# Baboi_v1_1.net
KiCad netlist of a schematic drawn in EAGLE
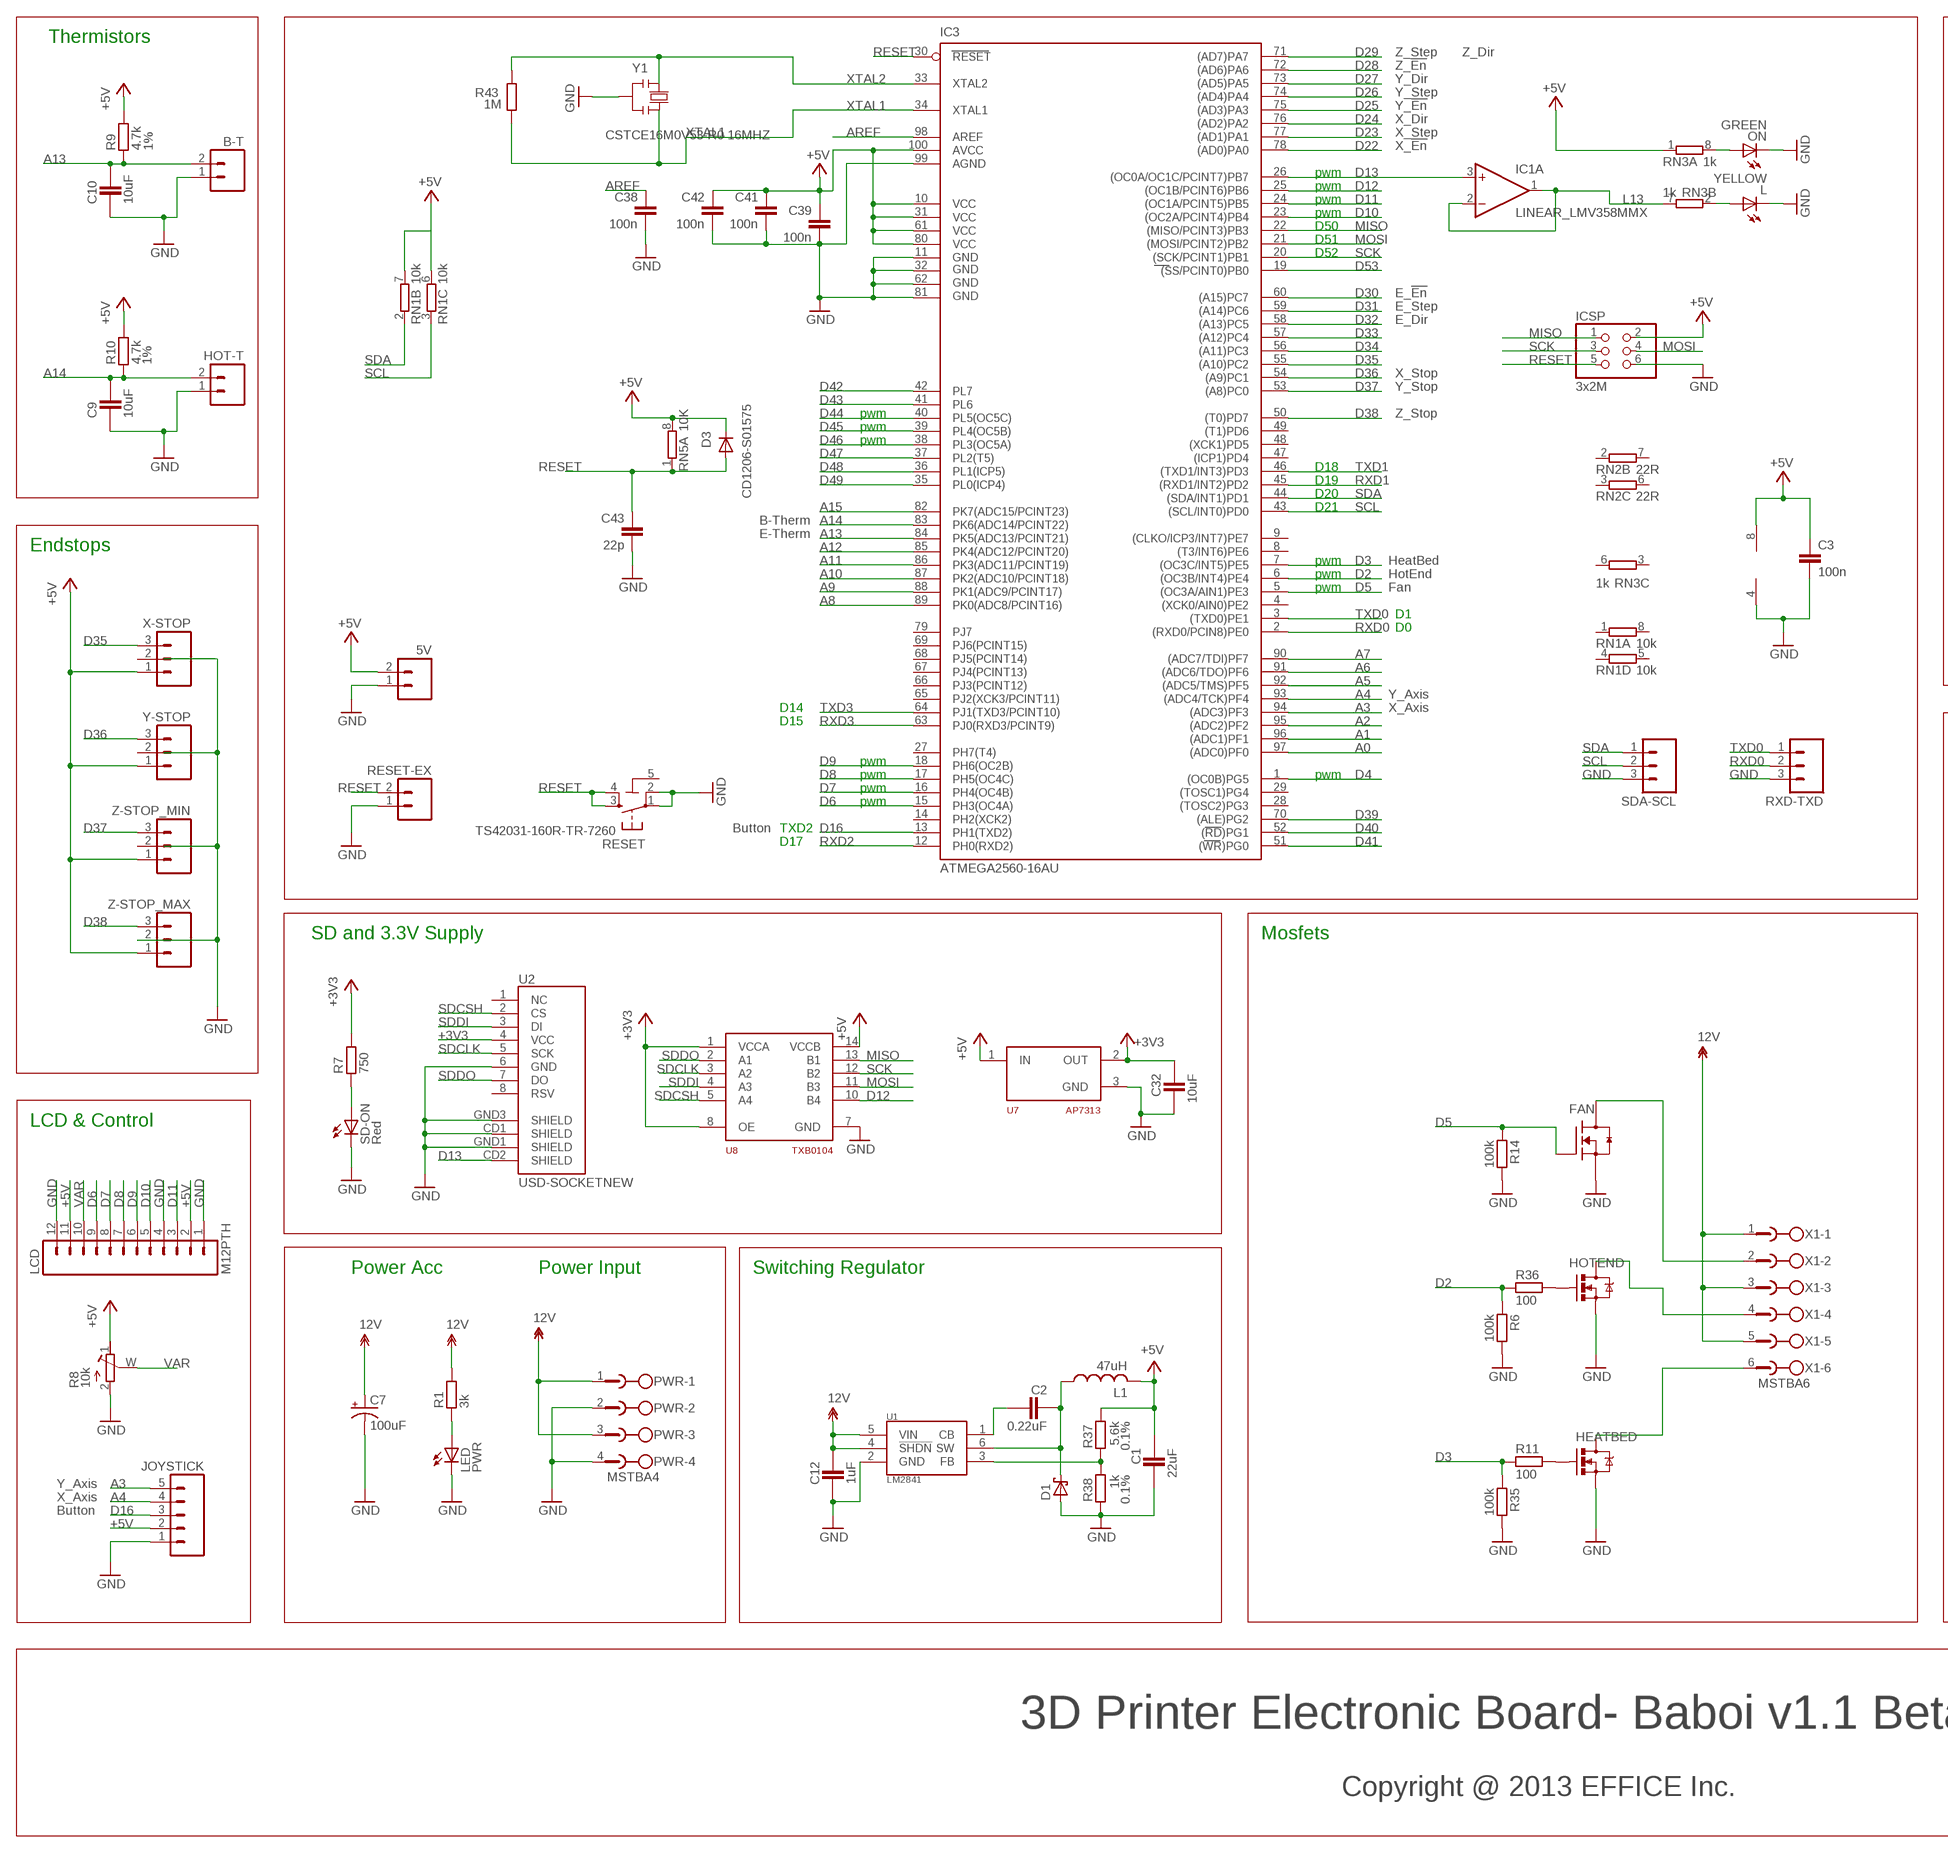
[diagram p0: schematic, sheet 1, part 1 of 2]
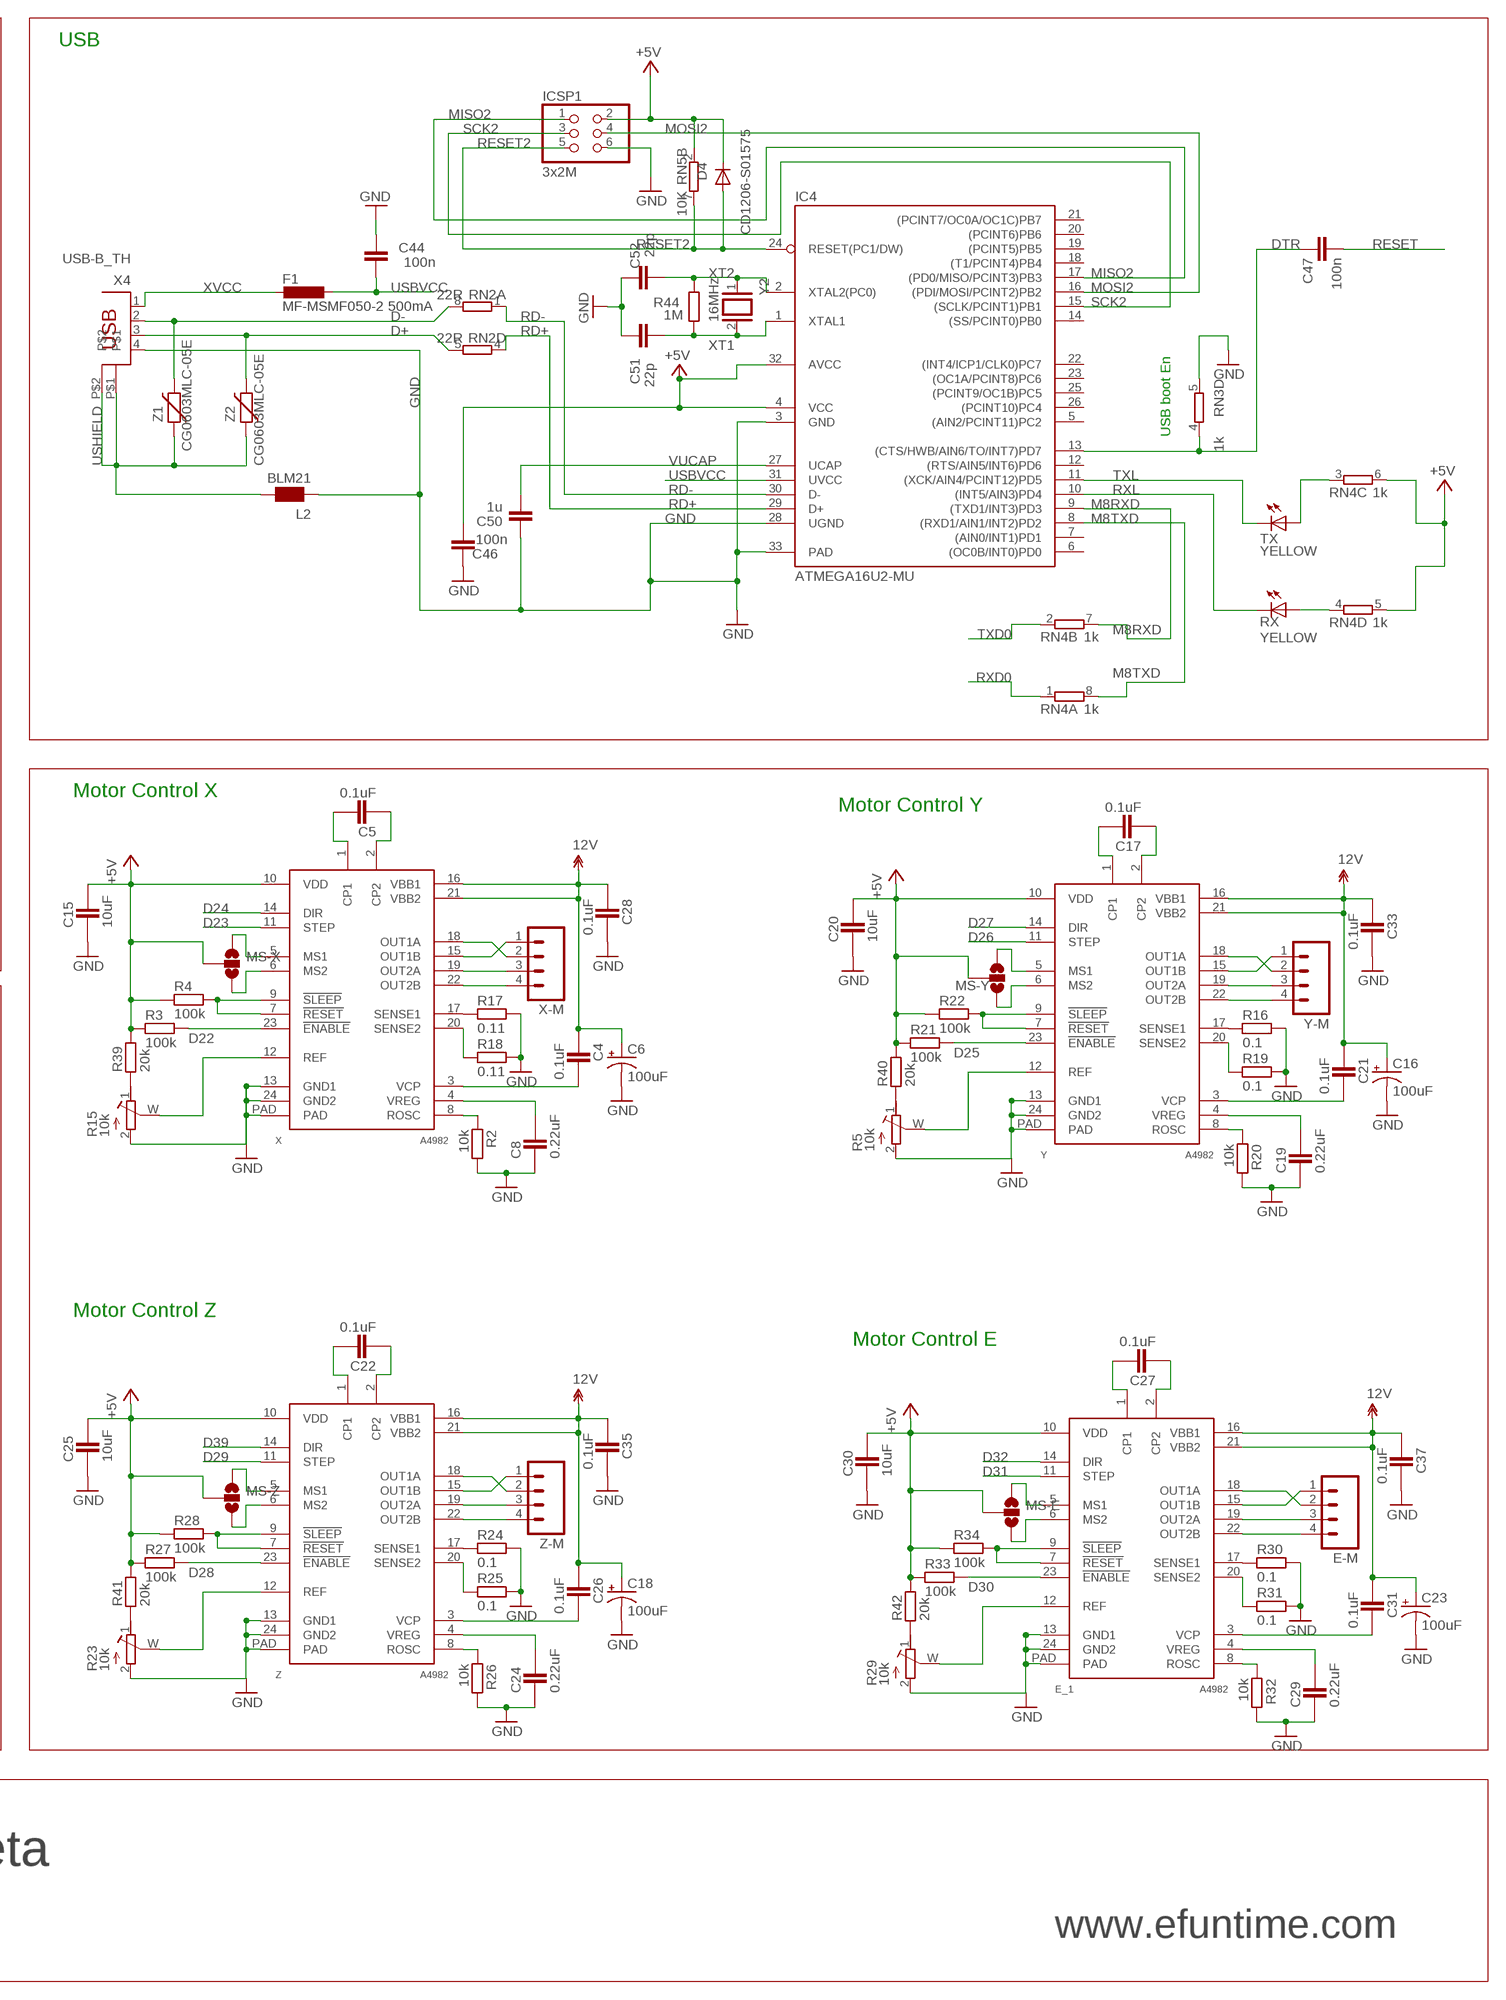
[diagram p1: schematic, sheet 1, part 2 of 2]

(export (version "E")
  (design (tool "Eeschema 10.0.6"))
  (components
    (comp (ref "5V")
      (value "M02PTH")
      (footprint "eagle-import:1X02")
      (libsource (lib "eagle-import") (part "M02PTH"))
    )
    (comp (ref "B-T")
      (value "M02PTH")
      (footprint "eagle-import:1X02")
      (libsource (lib "eagle-import") (part "M02PTH"))
    )
    (comp (ref "C1")
      (value "22uF")
      (footprint "eagle-import:CAPC2012X145AN")
      (libsource (lib "eagle-import") (part "CAPACITOR_0805"))
    )
    (comp (ref "C2")
      (value "0.22uF")
      (footprint "eagle-import:CAPC2012X145AN")
      (libsource (lib "eagle-import") (part "CAPACITOR_0805"))
    )
    (comp (ref "C3")
      (value "100n")
      (footprint "eagle-import:SMARTPRJ_C0603-ROUND")
      (libsource (lib "eagle-import") (part "SMARTPRJ_C-EUC0603"))
    )
    (comp (ref "C4")
      (value "0.1uF")
      (footprint "eagle-import:CAPC2012X145AN")
      (libsource (lib "eagle-import") (part "CAPACITOR_0805"))
    )
    (comp (ref "C5")
      (value "0.1uF")
      (footprint "eagle-import:CAPC2012X145AN")
      (libsource (lib "eagle-import") (part "CAPACITOR_0805"))
    )
    (comp (ref "C6")
      (value "100uF")
      (footprint "eagle-import:PANASONIC_D")
      (libsource (lib "eagle-import") (part "CPOL-USD"))
    )
    (comp (ref "C7")
      (value "100uF")
      (footprint "eagle-import:PANASONIC_D")
      (libsource (lib "eagle-import") (part "CPOL-USD"))
    )
    (comp (ref "C8")
      (value "0.22uF")
      (footprint "eagle-import:CAPC2012X145AN")
      (libsource (lib "eagle-import") (part "CAPACITOR_0805"))
    )
    (comp (ref "C9")
      (value "10uF")
      (footprint "eagle-import:CAPC2012X145AN")
      (libsource (lib "eagle-import") (part "CAPACITOR_0805"))
    )
    (comp (ref "C10")
      (value "10uF")
      (footprint "eagle-import:CAPC2012X145AN")
      (libsource (lib "eagle-import") (part "CAPACITOR_0805"))
    )
    (comp (ref "C12")
      (value "1uF")
      (footprint "eagle-import:CAPC2012X145AN")
      (libsource (lib "eagle-import") (part "CAPACITOR_0805"))
    )
    (comp (ref "C15")
      (value "10uF")
      (footprint "eagle-import:CAPC2012X145AN")
      (libsource (lib "eagle-import") (part "CAPACITOR_0805"))
    )
    (comp (ref "C16")
      (value "100uF")
      (footprint "eagle-import:PANASONIC_D")
      (libsource (lib "eagle-import") (part "CPOL-USD"))
    )
    (comp (ref "C17")
      (value "0.1uF")
      (footprint "eagle-import:CAPC2012X145AN")
      (libsource (lib "eagle-import") (part "CAPACITOR_0805"))
    )
    (comp (ref "C18")
      (value "100uF")
      (footprint "eagle-import:PANASONIC_D")
      (libsource (lib "eagle-import") (part "CPOL-USD"))
    )
    (comp (ref "C19")
      (value "0.22uF")
      (footprint "eagle-import:CAPC2012X145AN")
      (libsource (lib "eagle-import") (part "CAPACITOR_0805"))
    )
    (comp (ref "C20")
      (value "10uF")
      (footprint "eagle-import:CAPC2012X145AN")
      (libsource (lib "eagle-import") (part "CAPACITOR_0805"))
    )
    (comp (ref "C21")
      (value "0.1uF")
      (footprint "eagle-import:CAPC2012X145AN")
      (libsource (lib "eagle-import") (part "CAPACITOR_0805"))
    )
    (comp (ref "C22")
      (value "0.1uF")
      (footprint "eagle-import:CAPC2012X145AN")
      (libsource (lib "eagle-import") (part "CAPACITOR_0805"))
    )
    (comp (ref "C23")
      (value "100uF")
      (footprint "eagle-import:PANASONIC_D")
      (libsource (lib "eagle-import") (part "CPOL-USD"))
    )
    (comp (ref "C24")
      (value "0.22uF")
      (footprint "eagle-import:CAPC2012X145AN")
      (libsource (lib "eagle-import") (part "CAPACITOR_0805"))
    )
    (comp (ref "C25")
      (value "10uF")
      (footprint "eagle-import:CAPC2012X145AN")
      (libsource (lib "eagle-import") (part "CAPACITOR_0805"))
    )
    (comp (ref "C26")
      (value "0.1uF")
      (footprint "eagle-import:CAPC2012X145AN")
      (libsource (lib "eagle-import") (part "CAPACITOR_0805"))
    )
    (comp (ref "C27")
      (value "0.1uF")
      (footprint "eagle-import:CAPC2012X145AN")
      (libsource (lib "eagle-import") (part "CAPACITOR_0805"))
    )
    (comp (ref "C28")
      (value "0.1uF")
      (footprint "eagle-import:CAPC2012X145AN")
      (libsource (lib "eagle-import") (part "CAPACITOR_0805"))
    )
    (comp (ref "C29")
      (value "0.22uF")
      (footprint "eagle-import:CAPC2012X145AN")
      (libsource (lib "eagle-import") (part "CAPACITOR_0805"))
    )
    (comp (ref "C30")
      (value "10uF")
      (footprint "eagle-import:CAPC2012X145AN")
      (libsource (lib "eagle-import") (part "CAPACITOR_0805"))
    )
    (comp (ref "C31")
      (value "0.1uF")
      (footprint "eagle-import:CAPC2012X145AN")
      (libsource (lib "eagle-import") (part "CAPACITOR_0805"))
    )
    (comp (ref "C32")
      (value "10uF")
      (footprint "eagle-import:CAPC2012X145AN")
      (libsource (lib "eagle-import") (part "CAPACITOR_0805"))
    )
    (comp (ref "C33")
      (value "0.1uF")
      (footprint "eagle-import:CAPC2012X145AN")
      (libsource (lib "eagle-import") (part "CAPACITOR_0805"))
    )
    (comp (ref "C35")
      (value "0.1uF")
      (footprint "eagle-import:CAPC2012X145AN")
      (libsource (lib "eagle-import") (part "CAPACITOR_0805"))
    )
    (comp (ref "C37")
      (value "0.1uF")
      (footprint "eagle-import:CAPC2012X145AN")
      (libsource (lib "eagle-import") (part "CAPACITOR_0805"))
    )
    (comp (ref "C38")
      (value "100n")
      (footprint "eagle-import:C0603-ROUND")
      (libsource (lib "eagle-import") (part "C-EU0603-RND"))
    )
    (comp (ref "C39")
      (value "100n")
      (footprint "eagle-import:C0603-ROUND")
      (libsource (lib "eagle-import") (part "C-EU0603-RND"))
    )
    (comp (ref "C41")
      (value "100n")
      (footprint "eagle-import:C0603-ROUND")
      (libsource (lib "eagle-import") (part "C-EU0603-RND"))
    )
    (comp (ref "C42")
      (value "100n")
      (footprint "eagle-import:C0603-ROUND")
      (libsource (lib "eagle-import") (part "C-EU0603-RND"))
    )
    (comp (ref "C43")
      (value "22p")
      (footprint "eagle-import:C0603-ROUND")
      (libsource (lib "eagle-import") (part "C-EU0603-RND"))
    )
    (comp (ref "C44")
      (value "100n")
      (footprint "eagle-import:C0603-ROUND")
      (libsource (lib "eagle-import") (part "C-EU0603-RND"))
    )
    (comp (ref "C46")
      (value "100n")
      (footprint "eagle-import:C0603-ROUND")
      (libsource (lib "eagle-import") (part "C-EU0603-RND"))
    )
    (comp (ref "C47")
      (value "100n")
      (footprint "eagle-import:C0603-ROUND")
      (libsource (lib "eagle-import") (part "C-EU0603-RND"))
    )
    (comp (ref "C50")
      (value "1u")
      (footprint "eagle-import:C0603-ROUND")
      (libsource (lib "eagle-import") (part "C-EU0603-RND"))
    )
    (comp (ref "C51")
      (value "22p")
      (footprint "eagle-import:C0603-ROUND")
      (libsource (lib "eagle-import") (part "C-EU0603-RND"))
    )
    (comp (ref "C52")
      (value "22p")
      (footprint "eagle-import:C0603-ROUND")
      (libsource (lib "eagle-import") (part "C-EU0603-RND"))
    )
    (comp (ref "D1")
      (value "SCH-DIODESMA")
      (footprint "eagle-import:SMA")
      (libsource (lib "eagle-import") (part "SCH-DIODESMA"))
    )
    (comp (ref "D3")
      (value "CD1206-S01575")
      (footprint "eagle-import:MINIMELF")
      (libsource (lib "eagle-import") (part "DIODE-MINIMELF"))
    )
    (comp (ref "D4")
      (value "CD1206-S01575")
      (footprint "eagle-import:MINIMELF")
      (libsource (lib "eagle-import") (part "DIODE-MINIMELF"))
    )
    (comp (ref "E-M")
      (value "M04PTH")
      (footprint "eagle-import:1X04")
      (libsource (lib "eagle-import") (part "M04PTH"))
    )
    (comp (ref "E_1")
      (value "A4982")
      (footprint "eagle-import:TSSOP-24")
      (libsource (lib "eagle-import") (part "A4982"))
    )
    (comp (ref "F1")
      (value "MF-MSMF050-2 500mA")
      (footprint "eagle-import:L1812")
      (libsource (lib "eagle-import") (part "L-EUL1812"))
    )
    (comp (ref "FAN")
      (value "RFP30N06LE")
      (footprint "eagle-import:SOT95P280X135-3N")
      (libsource (lib "eagle-import") (part "MOSFET-NCH_SOT-23"))
    )
    (comp (ref "HEATBED")
      (value "RFP30N06LE")
      (footprint "eagle-import:TO220V")
      (libsource (lib "eagle-import") (part "MOSFET-NCHANNELPTH2"))
    )
    (comp (ref "HOT-T")
      (value "M02PTH")
      (footprint "eagle-import:1X02")
      (libsource (lib "eagle-import") (part "M02PTH"))
    )
    (comp (ref "HOTEND")
      (value "RFP30N06LE")
      (footprint "eagle-import:TO220V")
      (libsource (lib "eagle-import") (part "MOSFET-NCHANNELPTH2"))
    )
    (comp (ref "IC1")
      (value "LINEAR_LMV358MMX")
      (footprint "eagle-import:LINEAR_MSOP08")
      (libsource (lib "eagle-import") (part "LINEAR_LMV358?MMX"))
    )
    (comp (ref "IC3")
      (value "ATMEGA2560-16AU")
      (footprint "eagle-import:TQFP100")
      (libsource (lib "eagle-import") (part "ATMEGA2560AU2560-16"))
    )
    (comp (ref "IC4")
      (value "ATMEGA16U2-MU")
      (footprint "eagle-import:MLF32")
      (libsource (lib "eagle-import") (part "ATMEGA16U2-MU"))
    )
    (comp (ref "ICSP")
      (value "3x2M")
      (footprint "eagle-import:2X03")
      (libsource (lib "eagle-import") (part "PINHD-2X3"))
    )
    (comp (ref "ICSP1")
      (value "3x2M")
      (footprint "eagle-import:2X03")
      (libsource (lib "eagle-import") (part "PINHD-2X3"))
    )
    (comp (ref "JOYSTICK")
      (value "M05PTH")
      (footprint "eagle-import:1X05")
      (libsource (lib "eagle-import") (part "M05PTH"))
    )
    (comp (ref "L")
      (value "YELLOW")
      (footprint "eagle-import:CHIP-LED0805")
      (libsource (lib "eagle-import") (part "LEDCHIP-LED0805"))
    )
    (comp (ref "L1")
      (value "47uH")
      (footprint "eagle-import:SDR1006")
      (libsource (lib "eagle-import") (part "L-US"))
    )
    (comp (ref "L2")
      (value "BLM21")
      (footprint "eagle-import:0805")
      (libsource (lib "eagle-import") (part "WE-CBF_0805"))
    )
    (comp (ref "LCD")
      (value "M12PTH")
      (footprint "eagle-import:1X12")
      (libsource (lib "eagle-import") (part "M12PTH"))
    )
    (comp (ref "LED")
      (value "PWR")
      (footprint "eagle-import:CHIP-LED0805")
      (libsource (lib "eagle-import") (part "LEDCHIP-LED0805"))
    )
    (comp (ref "MS-E")
      (value "SOLDERJUMPER_2WAYCONNECTED")
      (footprint "eagle-import:SJ_3_CONNECTED")
      (libsource (lib "eagle-import") (part "SOLDERJUMPER_2WAYCONNECTED"))
    )
    (comp (ref "MS-X")
      (value "SOLDERJUMPER_2WAYCONNECTED")
      (footprint "eagle-import:SJ_3_CONNECTED")
      (libsource (lib "eagle-import") (part "SOLDERJUMPER_2WAYCONNECTED"))
    )
    (comp (ref "MS-Y")
      (value "SOLDERJUMPER_2WAYCONNECTED")
      (footprint "eagle-import:SJ_3_CONNECTED")
      (libsource (lib "eagle-import") (part "SOLDERJUMPER_2WAYCONNECTED"))
    )
    (comp (ref "MS-Z")
      (value "SOLDERJUMPER_2WAYCONNECTED")
      (footprint "eagle-import:SJ_3_CONNECTED")
      (libsource (lib "eagle-import") (part "SOLDERJUMPER_2WAYCONNECTED"))
    )
    (comp (ref "ON")
      (value "GREEN")
      (footprint "eagle-import:CHIP-LED0805")
      (libsource (lib "eagle-import") (part "LEDCHIP-LED0805"))
    )
    (comp (ref "PWR")
      (value "MSTBA4")
      (footprint "eagle-import:MSTBA4")
      (fields (field (name "MF") "FARNELL") (field (name "MPN") "1757268"))
      (libsource (lib "eagle-import") (part "MSTBA4"))
    )
    (comp (ref "R1")
      (value "3k")
      (footprint "eagle-import:RESC2012X70N")
      (libsource (lib "eagle-import") (part "RESISTOR_0805"))
    )
    (comp (ref "R2")
      (value "10k")
      (footprint "eagle-import:RESC2012X70N")
      (libsource (lib "eagle-import") (part "RESISTOR_0805"))
    )
    (comp (ref "R3")
      (value "100k")
      (footprint "eagle-import:RESC2012X70N")
      (libsource (lib "eagle-import") (part "RESISTOR_0805"))
    )
    (comp (ref "R4")
      (value "100k")
      (footprint "eagle-import:RESC2012X70N")
      (libsource (lib "eagle-import") (part "RESISTOR_0805"))
    )
    (comp (ref "R5")
      (value "10k")
      (footprint "eagle-import:RTRIM-ST4ETB")
      (libsource (lib "eagle-import") (part "RTRIM-ST-4EA"))
    )
    (comp (ref "R6")
      (value "100k")
      (footprint "eagle-import:RESC2012X70N")
      (libsource (lib "eagle-import") (part "RESISTOR_0805"))
    )
    (comp (ref "R7")
      (value "750")
      (footprint "eagle-import:RESC2012X70N")
      (libsource (lib "eagle-import") (part "RESISTOR_0805"))
    )
    (comp (ref "R8")
      (value "10k")
      (footprint "eagle-import:RTRIM-ST4ETB")
      (libsource (lib "eagle-import") (part "RTRIM-ST-4EA"))
    )
    (comp (ref "R9")
      (value "4.7k")
      (footprint "eagle-import:RESC2012X70N")
      (fields (field (name "TOLERANCE") "1%"))
      (libsource (lib "eagle-import") (part "RESISTOR_0805"))
    )
    (comp (ref "R10")
      (value "4.7k")
      (footprint "eagle-import:RESC2012X70N")
      (fields (field (name "TOLERANCE") "1%"))
      (libsource (lib "eagle-import") (part "RESISTOR_0805"))
    )
    (comp (ref "R11")
      (value "100")
      (footprint "eagle-import:RESC2012X70N")
      (libsource (lib "eagle-import") (part "RESISTOR_0805"))
    )
    (comp (ref "R14")
      (value "100k")
      (footprint "eagle-import:RESC2012X70N")
      (libsource (lib "eagle-import") (part "RESISTOR_0805"))
    )
    (comp (ref "R15")
      (value "10k")
      (footprint "eagle-import:RTRIM-ST4ETB")
      (libsource (lib "eagle-import") (part "RTRIM-ST-4EA"))
    )
    (comp (ref "R16")
      (value "0.1")
      (footprint "eagle-import:RESC2012X70N")
      (libsource (lib "eagle-import") (part "RESISTOR_0805"))
    )
    (comp (ref "R17")
      (value "0.11")
      (footprint "eagle-import:RESC2012X70N")
      (libsource (lib "eagle-import") (part "RESISTOR_0805"))
    )
    (comp (ref "R18")
      (value "0.11")
      (footprint "eagle-import:RESC2012X70N")
      (libsource (lib "eagle-import") (part "RESISTOR_0805"))
    )
    (comp (ref "R19")
      (value "0.1")
      (footprint "eagle-import:RESC2012X70N")
      (libsource (lib "eagle-import") (part "RESISTOR_0805"))
    )
    (comp (ref "R20")
      (value "10k")
      (footprint "eagle-import:RESC2012X70N")
      (libsource (lib "eagle-import") (part "RESISTOR_0805"))
    )
    (comp (ref "R21")
      (value "100k")
      (footprint "eagle-import:RESC2012X70N")
      (libsource (lib "eagle-import") (part "RESISTOR_0805"))
    )
    (comp (ref "R22")
      (value "100k")
      (footprint "eagle-import:RESC2012X70N")
      (libsource (lib "eagle-import") (part "RESISTOR_0805"))
    )
    (comp (ref "R23")
      (value "10k")
      (footprint "eagle-import:RTRIM-ST4ETB")
      (libsource (lib "eagle-import") (part "RTRIM-ST-4EA"))
    )
    (comp (ref "R24")
      (value "0.1")
      (footprint "eagle-import:RESC2012X70N")
      (libsource (lib "eagle-import") (part "RESISTOR_0805"))
    )
    (comp (ref "R25")
      (value "0.1")
      (footprint "eagle-import:RESC2012X70N")
      (libsource (lib "eagle-import") (part "RESISTOR_0805"))
    )
    (comp (ref "R26")
      (value "10k")
      (footprint "eagle-import:RESC2012X70N")
      (libsource (lib "eagle-import") (part "RESISTOR_0805"))
    )
    (comp (ref "R27")
      (value "100k")
      (footprint "eagle-import:RESC2012X70N")
      (libsource (lib "eagle-import") (part "RESISTOR_0805"))
    )
    (comp (ref "R28")
      (value "100k")
      (footprint "eagle-import:RESC2012X70N")
      (libsource (lib "eagle-import") (part "RESISTOR_0805"))
    )
    (comp (ref "R29")
      (value "10k")
      (footprint "eagle-import:RTRIM-ST4ETB")
      (libsource (lib "eagle-import") (part "RTRIM-ST-4EA"))
    )
    (comp (ref "R30")
      (value "0.1")
      (footprint "eagle-import:RESC2012X70N")
      (libsource (lib "eagle-import") (part "RESISTOR_0805"))
    )
    (comp (ref "R31")
      (value "0.1")
      (footprint "eagle-import:RESC2012X70N")
      (libsource (lib "eagle-import") (part "RESISTOR_0805"))
    )
    (comp (ref "R32")
      (value "10k")
      (footprint "eagle-import:RESC2012X70N")
      (libsource (lib "eagle-import") (part "RESISTOR_0805"))
    )
    (comp (ref "R33")
      (value "100k")
      (footprint "eagle-import:RESC2012X70N")
      (libsource (lib "eagle-import") (part "RESISTOR_0805"))
    )
    (comp (ref "R34")
      (value "100k")
      (footprint "eagle-import:RESC2012X70N")
      (libsource (lib "eagle-import") (part "RESISTOR_0805"))
    )
    (comp (ref "R35")
      (value "100k")
      (footprint "eagle-import:RESC2012X70N")
      (libsource (lib "eagle-import") (part "RESISTOR_0805"))
    )
    (comp (ref "R36")
      (value "100")
      (footprint "eagle-import:RESC2012X70N")
      (libsource (lib "eagle-import") (part "RESISTOR_0805"))
    )
    (comp (ref "R37")
      (value "5.6k")
      (footprint "eagle-import:RESC2012X70N")
      (fields (field (name "TOLERANCE") "0.1%"))
      (libsource (lib "eagle-import") (part "RESISTOR_0805"))
    )
    (comp (ref "R38")
      (value "1k")
      (footprint "eagle-import:RESC2012X70N")
      (fields (field (name "TOLERANCE") "0.1%"))
      (libsource (lib "eagle-import") (part "RESISTOR_0805"))
    )
    (comp (ref "R39")
      (value "20k")
      (footprint "eagle-import:RESC2012X70N")
      (libsource (lib "eagle-import") (part "RESISTOR_0805"))
    )
    (comp (ref "R40")
      (value "20k")
      (footprint "eagle-import:RESC2012X70N")
      (libsource (lib "eagle-import") (part "RESISTOR_0805"))
    )
    (comp (ref "R41")
      (value "20k")
      (footprint "eagle-import:RESC2012X70N")
      (libsource (lib "eagle-import") (part "RESISTOR_0805"))
    )
    (comp (ref "R42")
      (value "20k")
      (footprint "eagle-import:RESC2012X70N")
      (libsource (lib "eagle-import") (part "RESISTOR_0805"))
    )
    (comp (ref "R43")
      (value "1M")
      (footprint "eagle-import:R0603-ROUND")
      (libsource (lib "eagle-import") (part "R-EU_R0603"))
    )
    (comp (ref "R44")
      (value "1M")
      (footprint "eagle-import:R0603-ROUND")
      (libsource (lib "eagle-import") (part "R-EU_R0603"))
    )
    (comp (ref "RESET")
      (value "TS42031-160R-TR-7260")
      (footprint "eagle-import:TS42")
      (libsource (lib "eagle-import") (part "TS42"))
    )
    (comp (ref "RESET-EX")
      (value "M02PTH")
      (footprint "eagle-import:1X02")
      (libsource (lib "eagle-import") (part "M02PTH"))
    )
    (comp (ref "RN1")
      (value "10k")
      (footprint "eagle-import:RESISTOR-DIL_CAT16")
      (libsource (lib "eagle-import") (part "RESISTOR-DIL_4R-NCAT16"))
    )
    (comp (ref "RN2")
      (value "22R")
      (footprint "eagle-import:CAY16")
      (libsource (lib "eagle-import") (part "4R-NCAY16"))
    )
    (comp (ref "RN3")
      (value "1k")
      (footprint "eagle-import:CAY16")
      (libsource (lib "eagle-import") (part "4R-NCAY16"))
    )
    (comp (ref "RN4")
      (value "1k")
      (footprint "eagle-import:CAY16")
      (libsource (lib "eagle-import") (part "4R-NCAY16"))
    )
    (comp (ref "RN5")
      (value "10K")
      (footprint "eagle-import:CAT16")
      (libsource (lib "eagle-import") (part "4R-NCAT16"))
    )
    (comp (ref "RX")
      (value "YELLOW")
      (footprint "eagle-import:CHIP-LED0805")
      (libsource (lib "eagle-import") (part "LEDCHIP-LED0805"))
    )
    (comp (ref "RXD-TXD")
      (value "M03PTH")
      (footprint "eagle-import:1X03")
      (libsource (lib "eagle-import") (part "M03PTH"))
    )
    (comp (ref "SD-ON")
      (value "Red")
      (footprint "eagle-import:CHIP-LED0805")
      (libsource (lib "eagle-import") (part "LEDCHIP-LED0805"))
    )
    (comp (ref "SDA-SCL")
      (value "M03PTH")
      (footprint "eagle-import:1X03")
      (libsource (lib "eagle-import") (part "M03PTH"))
    )
    (comp (ref "TX")
      (value "YELLOW")
      (footprint "eagle-import:CHIP-LED0805")
      (libsource (lib "eagle-import") (part "LEDCHIP-LED0805"))
    )
    (comp (ref "U1")
      (value "LM2841")
      (footprint "eagle-import:TSOT6")
      (libsource (lib "eagle-import") (part "LM2841"))
    )
    (comp (ref "U2")
      (value "USD-SOCKETNEW")
      (footprint "eagle-import:MICRO-SD-SOCKET-PP")
      (libsource (lib "eagle-import") (part "USD-SOCKETNEW"))
    )
    (comp (ref "U7")
      (value "AP7313")
      (footprint "eagle-import:SOT23C")
      (libsource (lib "eagle-import") (part "AP7313"))
    )
    (comp (ref "U8")
      (value "TXB0104")
      (footprint "eagle-import:TSSOP14")
      (libsource (lib "eagle-import") (part "TXB0104"))
    )
    (comp (ref "X")
      (value "A4982")
      (footprint "eagle-import:TSSOP-24")
      (libsource (lib "eagle-import") (part "A4982"))
    )
    (comp (ref "X-M")
      (value "M04PTH")
      (footprint "eagle-import:1X04")
      (libsource (lib "eagle-import") (part "M04PTH"))
    )
    (comp (ref "X-STOP")
      (value "M03PTH")
      (footprint "eagle-import:1X03")
      (libsource (lib "eagle-import") (part "M03PTH"))
    )
    (comp (ref "X1")
      (value "MSTBA6")
      (footprint "eagle-import:MSTBA6")
      (fields (field (name "MF") "FARNELL") (field (name "MPN") "1757284"))
      (libsource (lib "eagle-import") (part "MSTBA6"))
    )
    (comp (ref "X4")
      (value "USB-B_TH")
      (footprint "eagle-import:PN61729")
      (libsource (lib "eagle-import") (part "PN61729"))
    )
    (comp (ref "Y")
      (value "A4982")
      (footprint "eagle-import:TSSOP-24")
      (libsource (lib "eagle-import") (part "A4982"))
    )
    (comp (ref "Y-M")
      (value "M04PTH")
      (footprint "eagle-import:1X04")
      (libsource (lib "eagle-import") (part "M04PTH"))
    )
    (comp (ref "Y-STOP")
      (value "M03PTH")
      (footprint "eagle-import:1X03")
      (libsource (lib "eagle-import") (part "M03PTH"))
    )
    (comp (ref "Y1")
      (value "CSTCE16M0V53-R0 16MHZ")
      (footprint "eagle-import:RESONATOR")
      (libsource (lib "eagle-import") (part "RESONATORMU"))
    )
    (comp (ref "Y2")
      (value "16MHz")
      (footprint "eagle-import:QS")
      (libsource (lib "eagle-import") (part "XTAL/S"))
    )
    (comp (ref "Z")
      (value "A4982")
      (footprint "eagle-import:TSSOP-24")
      (libsource (lib "eagle-import") (part "A4982"))
    )
    (comp (ref "Z-M")
      (value "M04PTH")
      (footprint "eagle-import:1X04")
      (libsource (lib "eagle-import") (part "M04PTH"))
    )
    (comp (ref "Z-STOP_MAX")
      (value "M03PTH")
      (footprint "eagle-import:1X03")
      (libsource (lib "eagle-import") (part "M03PTH"))
    )
    (comp (ref "Z-STOP_MIN")
      (value "M03PTH")
      (footprint "eagle-import:1X03")
      (libsource (lib "eagle-import") (part "M03PTH"))
    )
    (comp (ref "Z1")
      (value "CG0603MLC-05E")
      (footprint "eagle-import:CT_CN0603")
      (libsource (lib "eagle-import") (part "VARISTORCN0603"))
    )
    (comp (ref "Z2")
      (value "CG0603MLC-05E")
      (footprint "eagle-import:CT_CN0603")
      (libsource (lib "eagle-import") (part "VARISTORCN0603"))
    )
  )
  (nets
    (net (code "1") (name "+3V3") (class "Default")
      (node (ref "C32") (pin "1") (pinfunction "1_1") (pintype "passive"))
      (node (ref "R7") (pin "2") (pinfunction "2_2") (pintype "passive"))
      (node (ref "U2") (pin "4") (pinfunction "VCC_4") (pintype "bidirectional"))
      (node (ref "U7") (pin "2") (pinfunction "OUT_2") (pintype "power_in"))
      (node (ref "U8") (pin "1") (pinfunction "VCCA_1") (pintype "power_in"))
      (node (ref "U8") (pin "8") (pinfunction "OE_8") (pintype "input"))
    )
    (net (code "2") (name "+5V") (class "Default")
      (node (ref "5V") (pin "2") (pinfunction "2_2") (pintype "passive"))
      (node (ref "C1") (pin "1") (pinfunction "1_1") (pintype "passive"))
      (node (ref "C15") (pin "2") (pinfunction "2_2") (pintype "passive"))
      (node (ref "C20") (pin "2") (pinfunction "2_2") (pintype "passive"))
      (node (ref "C25") (pin "2") (pinfunction "2_2") (pintype "passive"))
      (node (ref "C3") (pin "1") (pinfunction "1_1") (pintype "passive"))
      (node (ref "C30") (pin "2") (pinfunction "2_2") (pintype "passive"))
      (node (ref "C39") (pin "1") (pinfunction "1_1") (pintype "passive"))
      (node (ref "C41") (pin "1") (pinfunction "1_1") (pintype "passive"))
      (node (ref "C42") (pin "1") (pinfunction "1_1") (pintype "passive"))
      (node (ref "C46") (pin "1") (pinfunction "1_1") (pintype "passive"))
      (node (ref "D3") (pin "C") (pinfunction "C_C") (pintype "passive"))
      (node (ref "D4") (pin "C") (pinfunction "C_C") (pintype "passive"))
      (node (ref "E_1") (pin "10") (pinfunction "VDD_10") (pintype "power_in"))
      (node (ref "IC1") (pin "8") (pinfunction "V+_8") (pintype "power_in"))
      (node (ref "IC3") (pin "10") (pinfunction "VCC_10") (pintype "power_in"))
      (node (ref "IC3") (pin "100") (pinfunction "AVCC_100") (pintype "power_in"))
      (node (ref "IC3") (pin "31") (pinfunction "VCC1_31") (pintype "power_in"))
      (node (ref "IC3") (pin "61") (pinfunction "VCC2_61") (pintype "power_in"))
      (node (ref "IC3") (pin "80") (pinfunction "VCC3_80") (pintype "power_in"))
      (node (ref "IC4") (pin "32") (pinfunction "AVCC_32") (pintype "power_in"))
      (node (ref "IC4") (pin "4") (pinfunction "VCC_4") (pintype "power_in"))
      (node (ref "ICSP") (pin "2") (pinfunction "2_2") (pintype "passive"))
      (node (ref "ICSP1") (pin "2") (pinfunction "2_2") (pintype "passive"))
      (node (ref "JOYSTICK") (pin "2") (pinfunction "2_2") (pintype "passive"))
      (node (ref "L1") (pin "P$2") (pinfunction "2_P$2") (pintype "passive"))
      (node (ref "LCD") (pin "11") (pinfunction "11_11") (pintype "passive"))
      (node (ref "LCD") (pin "2") (pinfunction "2_2") (pintype "passive"))
      (node (ref "MS-E") (pin "2") (pinfunction "2_2") (pintype "passive"))
      (node (ref "MS-X") (pin "2") (pinfunction "2_2") (pintype "passive"))
      (node (ref "MS-Y") (pin "2") (pinfunction "2_2") (pintype "passive"))
      (node (ref "MS-Z") (pin "2") (pinfunction "2_2") (pintype "passive"))
      (node (ref "R10") (pin "2") (pinfunction "2_2") (pintype "passive"))
      (node (ref "R21") (pin "1") (pinfunction "1_1") (pintype "passive"))
      (node (ref "R22") (pin "1") (pinfunction "1_1") (pintype "passive"))
      (node (ref "R27") (pin "1") (pinfunction "1_1") (pintype "passive"))
      (node (ref "R28") (pin "1") (pinfunction "1_1") (pintype "passive"))
      (node (ref "R3") (pin "1") (pinfunction "1_1") (pintype "passive"))
      (node (ref "R33") (pin "1") (pinfunction "1_1") (pintype "passive"))
      (node (ref "R34") (pin "1") (pinfunction "1_1") (pintype "passive"))
      (node (ref "R37") (pin "1") (pinfunction "1_1") (pintype "passive"))
      (node (ref "R39") (pin "2") (pinfunction "2_2") (pintype "passive"))
      (node (ref "R4") (pin "1") (pinfunction "1_1") (pintype "passive"))
      (node (ref "R40") (pin "2") (pinfunction "2_2") (pintype "passive"))
      (node (ref "R41") (pin "2") (pinfunction "2_2") (pintype "passive"))
      (node (ref "R42") (pin "2") (pinfunction "2_2") (pintype "passive"))
      (node (ref "R8") (pin "1") (pinfunction "A_1") (pintype "passive"))
      (node (ref "R9") (pin "2") (pinfunction "2_2") (pintype "passive"))
      (node (ref "RN1") (pin "6") (pinfunction "2_6") (pintype "passive"))
      (node (ref "RN1") (pin "7") (pinfunction "2_7") (pintype "passive"))
      (node (ref "RN3") (pin "1") (pinfunction "1_1") (pintype "passive"))
      (node (ref "RN4") (pin "5") (pinfunction "2_5") (pintype "passive"))
      (node (ref "RN4") (pin "6") (pinfunction "2_6") (pintype "passive"))
      (node (ref "RN5") (pin "2") (pinfunction "1_2") (pintype "passive"))
      (node (ref "RN5") (pin "8") (pinfunction "2_8") (pintype "passive"))
      (node (ref "U7") (pin "1") (pinfunction "IN_1") (pintype "power_in"))
      (node (ref "U8") (pin "14") (pinfunction "VCCB_14") (pintype "power_in"))
      (node (ref "X") (pin "10") (pinfunction "VDD_10") (pintype "power_in"))
      (node (ref "X-STOP") (pin "1") (pinfunction "1_1") (pintype "passive"))
      (node (ref "Y") (pin "10") (pinfunction "VDD_10") (pintype "power_in"))
      (node (ref "Y-STOP") (pin "1") (pinfunction "1_1") (pintype "passive"))
      (node (ref "Z") (pin "10") (pinfunction "VDD_10") (pintype "power_in"))
      (node (ref "Z-STOP_MAX") (pin "1") (pinfunction "1_1") (pintype "passive"))
      (node (ref "Z-STOP_MIN") (pin "1") (pinfunction "1_1") (pintype "passive"))
    )
    (net (code "3") (name "5-GND") (class "Default")
      (node (ref "RESET") (pin "5") (pinfunction "5-GND_5") (pintype "power_in"))
    )
    (net (code "4") (name "12V") (class "Default")
      (node (ref "C12") (pin "1") (pinfunction "1_1") (pintype "passive"))
      (node (ref "C16") (pin "+") (pinfunction "+_+") (pintype "passive"))
      (node (ref "C18") (pin "+") (pinfunction "+_+") (pintype "passive"))
      (node (ref "C21") (pin "1") (pinfunction "1_1") (pintype "passive"))
      (node (ref "C23") (pin "+") (pinfunction "+_+") (pintype "passive"))
      (node (ref "C26") (pin "1") (pinfunction "1_1") (pintype "passive"))
      (node (ref "C28") (pin "1") (pinfunction "1_1") (pintype "passive"))
      (node (ref "C31") (pin "1") (pinfunction "1_1") (pintype "passive"))
      (node (ref "C33") (pin "1") (pinfunction "1_1") (pintype "passive"))
      (node (ref "C35") (pin "1") (pinfunction "1_1") (pintype "passive"))
      (node (ref "C37") (pin "1") (pinfunction "1_1") (pintype "passive"))
      (node (ref "C4") (pin "1") (pinfunction "1_1") (pintype "passive"))
      (node (ref "C6") (pin "+") (pinfunction "+_+") (pintype "passive"))
      (node (ref "C7") (pin "+") (pinfunction "+_+") (pintype "passive"))
      (node (ref "E_1") (pin "16") (pinfunction "VBB1_16") (pintype "power_in"))
      (node (ref "E_1") (pin "21") (pinfunction "VBB2_21") (pintype "power_in"))
      (node (ref "PWR") (pin "1") (pinfunction "1_1") (pintype "passive"))
      (node (ref "PWR") (pin "3") (pinfunction "1_3") (pintype "passive"))
      (node (ref "R1") (pin "2") (pinfunction "2_2") (pintype "passive"))
      (node (ref "U1") (pin "4") (pinfunction "~{SHDN}_4") (pintype "input"))
      (node (ref "U1") (pin "5") (pinfunction "VIN_5") (pintype "power_in"))
      (node (ref "X") (pin "16") (pinfunction "VBB1_16") (pintype "power_in"))
      (node (ref "X") (pin "21") (pinfunction "VBB2_21") (pintype "power_in"))
      (node (ref "X1") (pin "1") (pinfunction "1_1") (pintype "passive"))
      (node (ref "X1") (pin "3") (pinfunction "1_3") (pintype "passive"))
      (node (ref "X1") (pin "5") (pinfunction "1_5") (pintype "passive"))
      (node (ref "Y") (pin "16") (pinfunction "VBB1_16") (pintype "power_in"))
      (node (ref "Y") (pin "21") (pinfunction "VBB2_21") (pintype "power_in"))
      (node (ref "Z") (pin "16") (pinfunction "VBB1_16") (pintype "power_in"))
      (node (ref "Z") (pin "21") (pinfunction "VBB2_21") (pintype "power_in"))
    )
    (net (code "5") (name "A0") (class "Default")
      (node (ref "IC3") (pin "97") (pinfunction "(ADC0)PF0_97") (pintype "bidirectional"))
    )
    (net (code "6") (name "A1") (class "Default")
      (node (ref "IC3") (pin "96") (pinfunction "(ADC1)PF1_96") (pintype "bidirectional"))
    )
    (net (code "7") (name "A2") (class "Default")
      (node (ref "IC3") (pin "95") (pinfunction "(ADC2)PF2_95") (pintype "bidirectional"))
    )
    (net (code "8") (name "A3") (class "Default")
      (node (ref "IC3") (pin "94") (pinfunction "(ADC3)PF3_94") (pintype "bidirectional"))
      (node (ref "JOYSTICK") (pin "5") (pinfunction "5_5") (pintype "passive"))
    )
    (net (code "9") (name "A4") (class "Default")
      (node (ref "IC3") (pin "93") (pinfunction "(ADC4/TCK)PF4_93") (pintype "bidirectional"))
      (node (ref "JOYSTICK") (pin "4") (pinfunction "4_4") (pintype "passive"))
    )
    (net (code "10") (name "A5") (class "Default")
      (node (ref "IC3") (pin "92") (pinfunction "(ADC5/TMS)PF5_92") (pintype "bidirectional"))
    )
    (net (code "11") (name "A6") (class "Default")
      (node (ref "IC3") (pin "91") (pinfunction "(ADC6/TDO)PF6_91") (pintype "bidirectional"))
    )
    (net (code "12") (name "A7") (class "Default")
      (node (ref "IC3") (pin "90") (pinfunction "(ADC7/TDI)PF7_90") (pintype "bidirectional"))
    )
    (net (code "13") (name "A8") (class "Default")
      (node (ref "IC3") (pin "89") (pinfunction "PK0(ADC8/PCINT16)_89") (pintype "bidirectional"))
    )
    (net (code "14") (name "A9") (class "Default")
      (node (ref "IC3") (pin "88") (pinfunction "PK1(ADC9/PCINT17)_88") (pintype "bidirectional"))
    )
    (net (code "15") (name "A10") (class "Default")
      (node (ref "IC3") (pin "87") (pinfunction "PK2(ADC10/PCINT18)_87") (pintype "bidirectional"))
    )
    (net (code "16") (name "A11") (class "Default")
      (node (ref "IC3") (pin "86") (pinfunction "PK3(ADC11/PCINT19)_86") (pintype "bidirectional"))
    )
    (net (code "17") (name "A12") (class "Default")
      (node (ref "IC3") (pin "85") (pinfunction "PK4(ADC12/PCINT20)_85") (pintype "bidirectional"))
    )
    (net (code "18") (name "A13") (class "Default")
      (node (ref "B-T") (pin "2") (pinfunction "2_2") (pintype "passive"))
      (node (ref "C10") (pin "2") (pinfunction "2_2") (pintype "passive"))
      (node (ref "IC3") (pin "84") (pinfunction "PK5(ADC13/PCINT21)_84") (pintype "bidirectional"))
      (node (ref "R9") (pin "1") (pinfunction "1_1") (pintype "passive"))
    )
    (net (code "19") (name "A14") (class "Default")
      (node (ref "C9") (pin "2") (pinfunction "2_2") (pintype "passive"))
      (node (ref "HOT-T") (pin "2") (pinfunction "2_2") (pintype "passive"))
      (node (ref "IC3") (pin "83") (pinfunction "PK6(ADC14/PCINT22)_83") (pintype "bidirectional"))
      (node (ref "R10") (pin "1") (pinfunction "1_1") (pintype "passive"))
    )
    (net (code "20") (name "A15") (class "Default")
      (node (ref "IC3") (pin "82") (pinfunction "PK7(ADC15/PCINT23)_82") (pintype "bidirectional"))
    )
    (net (code "21") (name "AREF") (class "Default")
      (node (ref "C38") (pin "1") (pinfunction "1_1") (pintype "passive"))
      (node (ref "IC3") (pin "98") (pinfunction "AREF_98") (pintype "bidirectional"))
    )
    (net (code "22") (name "D+") (class "Default")
      (node (ref "RN2") (pin "5") (pinfunction "2_5") (pintype "passive"))
      (node (ref "X4") (pin "3") (pinfunction "3_3") (pintype "bidirectional"))
      (node (ref "Z2") (pin "2") (pinfunction "2_2") (pintype "passive"))
    )
    (net (code "23") (name "D-") (class "Default")
      (node (ref "RN2") (pin "8") (pinfunction "2_8") (pintype "passive"))
      (node (ref "X4") (pin "2") (pinfunction "2_2") (pintype "bidirectional"))
      (node (ref "Z1") (pin "2") (pinfunction "2_2") (pintype "passive"))
    )
    (net (code "24") (name "D2") (class "Default")
      (node (ref "IC3") (pin "6") (pinfunction "(OC3B/INT4)PE4_6") (pintype "bidirectional"))
      (node (ref "R36") (pin "1") (pinfunction "1_1") (pintype "passive"))
      (node (ref "R6") (pin "1") (pinfunction "1_1") (pintype "passive"))
    )
    (net (code "25") (name "D3") (class "Default")
      (node (ref "IC3") (pin "7") (pinfunction "(OC3C/INT5)PE5_7") (pintype "bidirectional"))
      (node (ref "R11") (pin "1") (pinfunction "1_1") (pintype "passive"))
      (node (ref "R35") (pin "1") (pinfunction "1_1") (pintype "passive"))
    )
    (net (code "26") (name "D4") (class "Default")
      (node (ref "IC3") (pin "1") (pinfunction "(OC0B)PG5_1") (pintype "bidirectional"))
    )
    (net (code "27") (name "D5") (class "Default")
      (node (ref "FAN") (pin "1") (pinfunction "G_1") (pintype "passive"))
      (node (ref "IC3") (pin "5") (pinfunction "(OC3A/AIN1)PE3_5") (pintype "bidirectional"))
      (node (ref "R14") (pin "1") (pinfunction "1_1") (pintype "passive"))
    )
    (net (code "28") (name "D6") (class "Default")
      (node (ref "IC3") (pin "15") (pinfunction "PH3(OC4A)_15") (pintype "bidirectional"))
      (node (ref "LCD") (pin "9") (pinfunction "9_9") (pintype "passive"))
    )
    (net (code "29") (name "D7") (class "Default")
      (node (ref "IC3") (pin "16") (pinfunction "PH4(OC4B)_16") (pintype "bidirectional"))
      (node (ref "LCD") (pin "8") (pinfunction "8_8") (pintype "passive"))
    )
    (net (code "30") (name "D8") (class "Default")
      (node (ref "IC3") (pin "17") (pinfunction "PH5(OC4C)_17") (pintype "bidirectional"))
      (node (ref "LCD") (pin "7") (pinfunction "7_7") (pintype "passive"))
    )
    (net (code "31") (name "D9") (class "Default")
      (node (ref "IC3") (pin "18") (pinfunction "PH6(OC2B)_18") (pintype "bidirectional"))
      (node (ref "LCD") (pin "6") (pinfunction "6_6") (pintype "passive"))
    )
    (net (code "32") (name "D10") (class "Default")
      (node (ref "IC3") (pin "23") (pinfunction "(OC2A/PCINT4)PB4_23") (pintype "bidirectional"))
      (node (ref "LCD") (pin "5") (pinfunction "5_5") (pintype "passive"))
    )
    (net (code "33") (name "D11") (class "Default")
      (node (ref "IC3") (pin "24") (pinfunction "(OC1A/PCINT5)PB5_24") (pintype "bidirectional"))
      (node (ref "LCD") (pin "3") (pinfunction "3_3") (pintype "passive"))
    )
    (net (code "34") (name "D12") (class "Default")
      (node (ref "IC3") (pin "25") (pinfunction "(OC1B/PCINT6)PB6_25") (pintype "bidirectional"))
      (node (ref "U8") (pin "10") (pinfunction "B4_10") (pintype "bidirectional"))
    )
    (net (code "35") (name "D13") (class "Default")
      (node (ref "IC1") (pin "3") (pinfunction "+IN_3") (pintype "input"))
      (node (ref "IC3") (pin "26") (pinfunction "(OC0A/OC1C/PCINT7)PB7_26") (pintype "bidirectional"))
      (node (ref "U2") (pin "CD2") (pinfunction "SHIELD_CD2") (pintype "bidirectional"))
    )
    (net (code "36") (name "D16") (class "Default")
      (node (ref "IC3") (pin "13") (pinfunction "PH1(TXD2)_13") (pintype "bidirectional"))
      (node (ref "JOYSTICK") (pin "3") (pinfunction "3_3") (pintype "passive"))
    )
    (net (code "37") (name "D22") (class "Default")
      (node (ref "IC3") (pin "78") (pinfunction "(AD0)PA0_78") (pintype "bidirectional"))
      (node (ref "R3") (pin "2") (pinfunction "2_2") (pintype "passive"))
      (node (ref "X") (pin "23") (pinfunction "~{ENABLE}_23") (pintype "input"))
    )
    (net (code "38") (name "D23") (class "Default")
      (node (ref "IC3") (pin "77") (pinfunction "(AD1)PA1_77") (pintype "bidirectional"))
      (node (ref "X") (pin "11") (pinfunction "STEP_11") (pintype "input"))
    )
    (net (code "39") (name "D24") (class "Default")
      (node (ref "IC3") (pin "76") (pinfunction "(AD2)PA2_76") (pintype "bidirectional"))
      (node (ref "X") (pin "14") (pinfunction "DIR_14") (pintype "input"))
    )
    (net (code "40") (name "D25") (class "Default")
      (node (ref "IC3") (pin "75") (pinfunction "(AD3)PA3_75") (pintype "bidirectional"))
      (node (ref "R21") (pin "2") (pinfunction "2_2") (pintype "passive"))
      (node (ref "Y") (pin "23") (pinfunction "~{ENABLE}_23") (pintype "input"))
    )
    (net (code "41") (name "D26") (class "Default")
      (node (ref "IC3") (pin "74") (pinfunction "(AD4)PA4_74") (pintype "bidirectional"))
      (node (ref "Y") (pin "11") (pinfunction "STEP_11") (pintype "input"))
    )
    (net (code "42") (name "D27") (class "Default")
      (node (ref "IC3") (pin "73") (pinfunction "(AD5)PA5_73") (pintype "bidirectional"))
      (node (ref "Y") (pin "14") (pinfunction "DIR_14") (pintype "input"))
    )
    (net (code "43") (name "D28") (class "Default")
      (node (ref "IC3") (pin "72") (pinfunction "(AD6)PA6_72") (pintype "bidirectional"))
      (node (ref "R27") (pin "2") (pinfunction "2_2") (pintype "passive"))
      (node (ref "Z") (pin "23") (pinfunction "~{ENABLE}_23") (pintype "input"))
    )
    (net (code "44") (name "D29") (class "Default")
      (node (ref "IC3") (pin "71") (pinfunction "(AD7)PA7_71") (pintype "bidirectional"))
      (node (ref "Z") (pin "11") (pinfunction "STEP_11") (pintype "input"))
    )
    (net (code "45") (name "D30") (class "Default")
      (node (ref "E_1") (pin "23") (pinfunction "~{ENABLE}_23") (pintype "input"))
      (node (ref "IC3") (pin "60") (pinfunction "(A15)PC7_60") (pintype "bidirectional"))
      (node (ref "R33") (pin "2") (pinfunction "2_2") (pintype "passive"))
    )
    (net (code "46") (name "D31") (class "Default")
      (node (ref "E_1") (pin "11") (pinfunction "STEP_11") (pintype "input"))
      (node (ref "IC3") (pin "59") (pinfunction "(A14)PC6_59") (pintype "bidirectional"))
    )
    (net (code "47") (name "D32") (class "Default")
      (node (ref "E_1") (pin "14") (pinfunction "DIR_14") (pintype "input"))
      (node (ref "IC3") (pin "58") (pinfunction "(A13)PC5_58") (pintype "bidirectional"))
    )
    (net (code "48") (name "D33") (class "Default")
      (node (ref "IC3") (pin "57") (pinfunction "(A12)PC4_57") (pintype "bidirectional"))
    )
    (net (code "49") (name "D34") (class "Default")
      (node (ref "IC3") (pin "56") (pinfunction "(A11)PC3_56") (pintype "bidirectional"))
    )
    (net (code "50") (name "D35") (class "Default")
      (node (ref "IC3") (pin "55") (pinfunction "(A10)PC2_55") (pintype "bidirectional"))
      (node (ref "X-STOP") (pin "3") (pinfunction "3_3") (pintype "passive"))
    )
    (net (code "51") (name "D36") (class "Default")
      (node (ref "IC3") (pin "54") (pinfunction "(A9)PC1_54") (pintype "bidirectional"))
      (node (ref "Y-STOP") (pin "3") (pinfunction "3_3") (pintype "passive"))
    )
    (net (code "52") (name "D37") (class "Default")
      (node (ref "IC3") (pin "53") (pinfunction "(A8)PC0_53") (pintype "bidirectional"))
      (node (ref "Z-STOP_MIN") (pin "3") (pinfunction "3_3") (pintype "passive"))
    )
    (net (code "53") (name "D38") (class "Default")
      (node (ref "IC3") (pin "50") (pinfunction "(T0)PD7_50") (pintype "bidirectional"))
      (node (ref "Z-STOP_MAX") (pin "3") (pinfunction "3_3") (pintype "passive"))
    )
    (net (code "54") (name "D39") (class "Default")
      (node (ref "IC3") (pin "70") (pinfunction "(ALE)PG2_70") (pintype "bidirectional"))
      (node (ref "Z") (pin "14") (pinfunction "DIR_14") (pintype "input"))
    )
    (net (code "55") (name "D40") (class "Default")
      (node (ref "IC3") (pin "52") (pinfunction "(RD)PG1_52") (pintype "bidirectional"))
    )
    (net (code "56") (name "D41") (class "Default")
      (node (ref "IC3") (pin "51") (pinfunction "(WR)PG0_51") (pintype "bidirectional"))
    )
    (net (code "57") (name "D42") (class "Default")
      (node (ref "IC3") (pin "42") (pinfunction "PL7_42") (pintype "bidirectional"))
    )
    (net (code "58") (name "D43") (class "Default")
      (node (ref "IC3") (pin "41") (pinfunction "PL6_41") (pintype "bidirectional"))
    )
    (net (code "59") (name "D44") (class "Default")
      (node (ref "IC3") (pin "40") (pinfunction "PL5(OC5C)_40") (pintype "bidirectional"))
    )
    (net (code "60") (name "D45") (class "Default")
      (node (ref "IC3") (pin "39") (pinfunction "PL4(OC5B)_39") (pintype "bidirectional"))
    )
    (net (code "61") (name "D46") (class "Default")
      (node (ref "IC3") (pin "38") (pinfunction "PL3(OC5A)_38") (pintype "bidirectional"))
    )
    (net (code "62") (name "D47") (class "Default")
      (node (ref "IC3") (pin "37") (pinfunction "PL2(T5)_37") (pintype "bidirectional"))
    )
    (net (code "63") (name "D48") (class "Default")
      (node (ref "IC3") (pin "36") (pinfunction "PL1(ICP5)_36") (pintype "bidirectional"))
    )
    (net (code "64") (name "D49") (class "Default")
      (node (ref "IC3") (pin "35") (pinfunction "PL0(ICP4)_35") (pintype "bidirectional"))
    )
    (net (code "65") (name "D53") (class "Default")
      (node (ref "IC3") (pin "19") (pinfunction "(SS/PCINT0)PB0_19") (pintype "bidirectional"))
    )
    (net (code "66") (name "DTR") (class "Default")
      (node (ref "C47") (pin "1") (pinfunction "1_1") (pintype "passive"))
      (node (ref "IC4") (pin "13") (pinfunction "(CTS/HWB/AIN6/TO/INT7)PD7_13") (pintype "bidirectional"))
      (node (ref "RN3") (pin "4") (pinfunction "1_4") (pintype "passive"))
    )
    (net (code "67") (name "GND") (class "Default")
      (node (ref "5V") (pin "1") (pinfunction "1_1") (pintype "passive"))
      (node (ref "B-T") (pin "1") (pinfunction "1_1") (pintype "passive"))
      (node (ref "C1") (pin "2") (pinfunction "2_2") (pintype "passive"))
      (node (ref "C10") (pin "1") (pinfunction "1_1") (pintype "passive"))
      (node (ref "C12") (pin "2") (pinfunction "2_2") (pintype "passive"))
      (node (ref "C15") (pin "1") (pinfunction "1_1") (pintype "passive"))
      (node (ref "C16") (pin "-") (pinfunction "-_-") (pintype "passive"))
      (node (ref "C18") (pin "-") (pinfunction "-_-") (pintype "passive"))
      (node (ref "C19") (pin "1") (pinfunction "1_1") (pintype "passive"))
      (node (ref "C20") (pin "1") (pinfunction "1_1") (pintype "passive"))
      (node (ref "C23") (pin "-") (pinfunction "-_-") (pintype "passive"))
      (node (ref "C24") (pin "1") (pinfunction "1_1") (pintype "passive"))
      (node (ref "C25") (pin "1") (pinfunction "1_1") (pintype "passive"))
      (node (ref "C28") (pin "2") (pinfunction "2_2") (pintype "passive"))
      (node (ref "C29") (pin "1") (pinfunction "1_1") (pintype "passive"))
      (node (ref "C3") (pin "2") (pinfunction "2_2") (pintype "passive"))
      (node (ref "C30") (pin "1") (pinfunction "1_1") (pintype "passive"))
      (node (ref "C32") (pin "2") (pinfunction "2_2") (pintype "passive"))
      (node (ref "C33") (pin "2") (pinfunction "2_2") (pintype "passive"))
      (node (ref "C35") (pin "2") (pinfunction "2_2") (pintype "passive"))
      (node (ref "C37") (pin "2") (pinfunction "2_2") (pintype "passive"))
      (node (ref "C38") (pin "2") (pinfunction "2_2") (pintype "passive"))
      (node (ref "C39") (pin "2") (pinfunction "2_2") (pintype "passive"))
      (node (ref "C41") (pin "2") (pinfunction "2_2") (pintype "passive"))
      (node (ref "C42") (pin "2") (pinfunction "2_2") (pintype "passive"))
      (node (ref "C43") (pin "2") (pinfunction "2_2") (pintype "passive"))
      (node (ref "C44") (pin "2") (pinfunction "2_2") (pintype "passive"))
      (node (ref "C46") (pin "2") (pinfunction "2_2") (pintype "passive"))
      (node (ref "C50") (pin "2") (pinfunction "2_2") (pintype "passive"))
      (node (ref "C51") (pin "2") (pinfunction "2_2") (pintype "passive"))
      (node (ref "C52") (pin "2") (pinfunction "2_2") (pintype "passive"))
      (node (ref "C6") (pin "-") (pinfunction "-_-") (pintype "passive"))
      (node (ref "C7") (pin "-") (pinfunction "-_-") (pintype "passive"))
      (node (ref "C8") (pin "1") (pinfunction "1_1") (pintype "passive"))
      (node (ref "C9") (pin "1") (pinfunction "1_1") (pintype "passive"))
      (node (ref "D1") (pin "A") (pinfunction "A_A") (pintype "passive"))
      (node (ref "E_1") (pin "13") (pinfunction "GND1_13") (pintype "power_in"))
      (node (ref "E_1") (pin "24") (pinfunction "GND2_24") (pintype "power_in"))
      (node (ref "E_1") (pin "PAD") (pinfunction "PAD_PAD") (pintype "power_in"))
      (node (ref "FAN") (pin "2") (pinfunction "S_2") (pintype "passive"))
      (node (ref "HEATBED") (pin "3") (pinfunction "S_3") (pintype "passive"))
      (node (ref "HOT-T") (pin "1") (pinfunction "1_1") (pintype "passive"))
      (node (ref "HOTEND") (pin "3") (pinfunction "S_3") (pintype "passive"))
      (node (ref "IC1") (pin "4") (pinfunction "V-_4") (pintype "power_in"))
      (node (ref "IC3") (pin "11") (pinfunction "GND_11") (pintype "power_in"))
      (node (ref "IC3") (pin "32") (pinfunction "GND1_32") (pintype "power_in"))
      (node (ref "IC3") (pin "62") (pinfunction "GND2_62") (pintype "power_in"))
      (node (ref "IC3") (pin "81") (pinfunction "GND3_81") (pintype "power_in"))
      (node (ref "IC3") (pin "99") (pinfunction "AGND_99") (pintype "power_in"))
      (node (ref "IC4") (pin "28") (pinfunction "UGND_28") (pintype "power_in"))
      (node (ref "IC4") (pin "3") (pinfunction "GND_3") (pintype "power_in"))
      (node (ref "IC4") (pin "33") (pinfunction "PAD_33") (pintype "power_in"))
      (node (ref "ICSP") (pin "6") (pinfunction "6_6") (pintype "passive"))
      (node (ref "ICSP1") (pin "6") (pinfunction "6_6") (pintype "passive"))
      (node (ref "JOYSTICK") (pin "1") (pinfunction "1_1") (pintype "passive"))
      (node (ref "L") (pin "C") (pinfunction "C_C") (pintype "passive"))
      (node (ref "L2") (pin "1") (pinfunction "1_1") (pintype "passive"))
      (node (ref "LCD") (pin "1") (pinfunction "1_1") (pintype "passive"))
      (node (ref "LCD") (pin "12") (pinfunction "12_12") (pintype "passive"))
      (node (ref "LCD") (pin "4") (pinfunction "4_4") (pintype "passive"))
      (node (ref "LED") (pin "C") (pinfunction "C_C") (pintype "passive"))
      (node (ref "ON") (pin "C") (pinfunction "C_C") (pintype "passive"))
      (node (ref "PWR") (pin "2") (pinfunction "1_2") (pintype "passive"))
      (node (ref "PWR") (pin "4") (pinfunction "1_4") (pintype "passive"))
      (node (ref "R14") (pin "2") (pinfunction "2_2") (pintype "passive"))
      (node (ref "R15") (pin "2") (pinfunction "E_2") (pintype "passive"))
      (node (ref "R16") (pin "2") (pinfunction "2_2") (pintype "passive"))
      (node (ref "R17") (pin "2") (pinfunction "2_2") (pintype "passive"))
      (node (ref "R18") (pin "2") (pinfunction "2_2") (pintype "passive"))
      (node (ref "R19") (pin "2") (pinfunction "2_2") (pintype "passive"))
      (node (ref "R2") (pin "2") (pinfunction "2_2") (pintype "passive"))
      (node (ref "R20") (pin "2") (pinfunction "2_2") (pintype "passive"))
      (node (ref "R23") (pin "2") (pinfunction "E_2") (pintype "passive"))
      (node (ref "R24") (pin "2") (pinfunction "2_2") (pintype "passive"))
      (node (ref "R25") (pin "2") (pinfunction "2_2") (pintype "passive"))
      (node (ref "R26") (pin "2") (pinfunction "2_2") (pintype "passive"))
      (node (ref "R29") (pin "2") (pinfunction "E_2") (pintype "passive"))
      (node (ref "R30") (pin "2") (pinfunction "2_2") (pintype "passive"))
      (node (ref "R31") (pin "2") (pinfunction "2_2") (pintype "passive"))
      (node (ref "R32") (pin "2") (pinfunction "2_2") (pintype "passive"))
      (node (ref "R35") (pin "2") (pinfunction "2_2") (pintype "passive"))
      (node (ref "R38") (pin "2") (pinfunction "2_2") (pintype "passive"))
      (node (ref "R5") (pin "2") (pinfunction "E_2") (pintype "passive"))
      (node (ref "R6") (pin "2") (pinfunction "2_2") (pintype "passive"))
      (node (ref "R8") (pin "2") (pinfunction "E_2") (pintype "passive"))
      (node (ref "RESET") (pin "1") (pinfunction "1_1") (pintype "passive"))
      (node (ref "RESET") (pin "2") (pinfunction "2_2") (pintype "passive"))
      (node (ref "RESET-EX") (pin "1") (pinfunction "1_1") (pintype "passive"))
      (node (ref "RN3") (pin "5") (pinfunction "2_5") (pintype "passive"))
      (node (ref "RXD-TXD") (pin "3") (pinfunction "3_3") (pintype "passive"))
      (node (ref "SD-ON") (pin "C") (pinfunction "C_C") (pintype "passive"))
      (node (ref "SDA-SCL") (pin "3") (pinfunction "3_3") (pintype "passive"))
      (node (ref "U1") (pin "2") (pinfunction "GND_2") (pintype "power_in"))
      (node (ref "U2") (pin "6") (pinfunction "GND_6") (pintype "bidirectional"))
      (node (ref "U2") (pin "CD1") (pinfunction "SHIELD_CD1") (pintype "bidirectional"))
      (node (ref "U2") (pin "GND1") (pinfunction "SHIELD_GND1") (pintype "bidirectional"))
      (node (ref "U2") (pin "GND3") (pinfunction "SHIELD_GND3") (pintype "bidirectional"))
      (node (ref "U7") (pin "3") (pinfunction "GND_3") (pintype "power_in"))
      (node (ref "U8") (pin "7") (pinfunction "GND_7") (pintype "power_in"))
      (node (ref "X") (pin "13") (pinfunction "GND1_13") (pintype "power_in"))
      (node (ref "X") (pin "24") (pinfunction "GND2_24") (pintype "power_in"))
      (node (ref "X") (pin "PAD") (pinfunction "PAD_PAD") (pintype "power_in"))
      (node (ref "X4") (pin "4") (pinfunction "4_4") (pintype "bidirectional"))
      (node (ref "Y") (pin "13") (pinfunction "GND1_13") (pintype "power_in"))
      (node (ref "Y") (pin "24") (pinfunction "GND2_24") (pintype "power_in"))
      (node (ref "Y") (pin "PAD") (pinfunction "PAD_PAD") (pintype "power_in"))
      (node (ref "Y1") (pin "2") (pinfunction "2_2") (pintype "passive"))
      (node (ref "Z") (pin "13") (pinfunction "GND1_13") (pintype "power_in"))
      (node (ref "Z") (pin "24") (pinfunction "GND2_24") (pintype "power_in"))
      (node (ref "Z") (pin "PAD") (pinfunction "PAD_PAD") (pintype "power_in"))
      (node (ref "Z-STOP_MAX") (pin "2") (pinfunction "2_2") (pintype "passive"))
    )
    (net (code "68") (name "L13") (class "Default")
      (node (ref "IC1") (pin "1") (pinfunction "OUT_1") (pintype "output"))
      (node (ref "IC1") (pin "2") (pinfunction "-IN_2") (pintype "input"))
      (node (ref "RN3") (pin "7") (pinfunction "2_7") (pintype "passive"))
    )
    (net (code "69") (name "M8RXD") (class "Default")
      (node (ref "IC4") (pin "9") (pinfunction "(TXD1/INT3)PD3_9") (pintype "bidirectional"))
      (node (ref "RN4") (pin "7") (pinfunction "2_7") (pintype "passive"))
    )
    (net (code "70") (name "M8TXD") (class "Default")
      (node (ref "IC4") (pin "8") (pinfunction "(RXD1/AIN1/INT2)PD2_8") (pintype "bidirectional"))
      (node (ref "RN4") (pin "8") (pinfunction "2_8") (pintype "passive"))
    )
    (net (code "71") (name "MISO") (class "Default")
      (node (ref "IC3") (pin "22") (pinfunction "(MISO/PCINT3)PB3_22") (pintype "bidirectional"))
      (node (ref "ICSP") (pin "1") (pinfunction "1_1") (pintype "passive"))
      (node (ref "U8") (pin "13") (pinfunction "B1_13") (pintype "bidirectional"))
    )
    (net (code "72") (name "MISO2") (class "Default")
      (node (ref "IC4") (pin "17") (pinfunction "(PD0/MISO/PCINT3)PB3_17") (pintype "bidirectional"))
      (node (ref "ICSP1") (pin "1") (pinfunction "1_1") (pintype "passive"))
    )
    (net (code "73") (name "MOSI") (class "Default")
      (node (ref "IC3") (pin "21") (pinfunction "(MOSI/PCINT2)PB2_21") (pintype "bidirectional"))
      (node (ref "ICSP") (pin "4") (pinfunction "4_4") (pintype "passive"))
      (node (ref "U8") (pin "11") (pinfunction "B3_11") (pintype "bidirectional"))
    )
    (net (code "74") (name "MOSI2") (class "Default")
      (node (ref "IC4") (pin "16") (pinfunction "(PDI/MOSI/PCINT2)PB2_16") (pintype "bidirectional"))
      (node (ref "ICSP1") (pin "4") (pinfunction "4_4") (pintype "passive"))
    )
    (net (code "75") (name "Net-(C43-Pad1)") (class "Default")
      (node (ref "C43") (pin "1") (pinfunction "1_1") (pintype "passive"))
      (node (ref "D3") (pin "A") (pinfunction "A_A") (pintype "passive"))
      (node (ref "RN5") (pin "1") (pinfunction "1_1") (pintype "passive"))
    )
    (net (code "76") (name "Net-(E_1-CP1)") (class "Default")
      (node (ref "C27") (pin "2") (pinfunction "2_2") (pintype "passive"))
      (node (ref "E_1") (pin "1") (pinfunction "CP1_1") (pintype "passive"))
    )
    (net (code "77") (name "Net-(E_1-CP2)") (class "Default")
      (node (ref "C27") (pin "1") (pinfunction "1_1") (pintype "passive"))
      (node (ref "E_1") (pin "2") (pinfunction "CP2_2") (pintype "passive"))
    )
    (net (code "78") (name "Net-(E_1-MS1)") (class "Default")
      (node (ref "E_1") (pin "5") (pinfunction "MS1_5") (pintype "input"))
      (node (ref "MS-E") (pin "1") (pinfunction "1_1") (pintype "passive"))
    )
    (net (code "79") (name "Net-(E_1-MS2)") (class "Default")
      (node (ref "E_1") (pin "6") (pinfunction "MS2_6") (pintype "input"))
      (node (ref "MS-E") (pin "3") (pinfunction "3_3") (pintype "passive"))
    )
    (net (code "80") (name "Net-(E_1-OUT1A)") (class "Default")
      (node (ref "E-M") (pin "2") (pinfunction "2_2") (pintype "passive"))
      (node (ref "E_1") (pin "18") (pinfunction "OUT1A_18") (pintype "output"))
    )
    (net (code "81") (name "Net-(E_1-OUT1B)") (class "Default")
      (node (ref "E-M") (pin "1") (pinfunction "1_1") (pintype "passive"))
      (node (ref "E_1") (pin "15") (pinfunction "OUT1B_15") (pintype "output"))
    )
    (net (code "82") (name "Net-(E_1-OUT2A)") (class "Default")
      (node (ref "E-M") (pin "3") (pinfunction "3_3") (pintype "passive"))
      (node (ref "E_1") (pin "19") (pinfunction "OUT2A_19") (pintype "output"))
    )
    (net (code "83") (name "Net-(E_1-OUT2B)") (class "Default")
      (node (ref "E-M") (pin "4") (pinfunction "4_4") (pintype "passive"))
      (node (ref "E_1") (pin "22") (pinfunction "OUT2B_22") (pintype "output"))
    )
    (net (code "84") (name "Net-(E_1-REF)") (class "Default")
      (node (ref "E_1") (pin "12") (pinfunction "REF_12") (pintype "input"))
      (node (ref "R29") (pin "W") (pinfunction "S_W") (pintype "passive"))
    )
    (net (code "85") (name "Net-(E_1-ROSC)") (class "Default")
      (node (ref "E_1") (pin "8") (pinfunction "ROSC_8") (pintype "passive"))
      (node (ref "R32") (pin "1") (pinfunction "1_1") (pintype "passive"))
    )
    (net (code "86") (name "Net-(E_1-SENSE1)") (class "Default")
      (node (ref "E_1") (pin "17") (pinfunction "SENSE1_17") (pintype "passive"))
      (node (ref "R30") (pin "1") (pinfunction "1_1") (pintype "passive"))
    )
    (net (code "87") (name "Net-(E_1-SENSE2)") (class "Default")
      (node (ref "E_1") (pin "20") (pinfunction "SENSE2_20") (pintype "passive"))
      (node (ref "R31") (pin "1") (pinfunction "1_1") (pintype "passive"))
    )
    (net (code "88") (name "Net-(E_1-VCP)") (class "Default")
      (node (ref "C31") (pin "2") (pinfunction "2_2") (pintype "passive"))
      (node (ref "E_1") (pin "3") (pinfunction "VCP_3") (pintype "passive"))
    )
    (net (code "89") (name "Net-(E_1-VREG)") (class "Default")
      (node (ref "C29") (pin "2") (pinfunction "2_2") (pintype "passive"))
      (node (ref "E_1") (pin "4") (pinfunction "VREG_4") (pintype "passive"))
    )
    (net (code "90") (name "Net-(E_1-~{RESET})") (class "Default")
      (node (ref "E_1") (pin "7") (pinfunction "~{RESET}_7") (pintype "input"))
      (node (ref "E_1") (pin "9") (pinfunction "~{SLEEP}_9") (pintype "input"))
      (node (ref "R34") (pin "2") (pinfunction "2_2") (pintype "passive"))
    )
    (net (code "91") (name "Net-(FAN-D)") (class "Default")
      (node (ref "FAN") (pin "3") (pinfunction "D_3") (pintype "passive"))
      (node (ref "X1") (pin "2") (pinfunction "1_2") (pintype "passive"))
    )
    (net (code "92") (name "Net-(HEATBED-D)") (class "Default")
      (node (ref "HEATBED") (pin "2") (pinfunction "D_2") (pintype "passive"))
      (node (ref "X1") (pin "6") (pinfunction "1_6") (pintype "passive"))
    )
    (net (code "93") (name "Net-(HEATBED-G)") (class "Default")
      (node (ref "HEATBED") (pin "1") (pinfunction "G_1") (pintype "passive"))
      (node (ref "R11") (pin "2") (pinfunction "2_2") (pintype "passive"))
    )
    (net (code "94") (name "Net-(HOTEND-D)") (class "Default")
      (node (ref "HOTEND") (pin "2") (pinfunction "D_2") (pintype "passive"))
      (node (ref "X1") (pin "4") (pinfunction "1_4") (pintype "passive"))
    )
    (net (code "95") (name "Net-(HOTEND-G)") (class "Default")
      (node (ref "HOTEND") (pin "1") (pinfunction "G_1") (pintype "passive"))
      (node (ref "R36") (pin "2") (pinfunction "2_2") (pintype "passive"))
    )
    (net (code "96") (name "Net-(L1-1)") (class "Default")
      (node (ref "C2") (pin "1") (pinfunction "1_1") (pintype "passive"))
      (node (ref "D1") (pin "C") (pinfunction "C_C") (pintype "passive"))
      (node (ref "L1") (pin "P$1") (pinfunction "1_P$1") (pintype "passive"))
      (node (ref "U1") (pin "6") (pinfunction "SW_6") (pintype "passive"))
    )
    (net (code "97") (name "Net-(LED-PadA)") (class "Default")
      (node (ref "LED") (pin "A") (pinfunction "A_A") (pintype "passive"))
      (node (ref "R1") (pin "1") (pinfunction "1_1") (pintype "passive"))
    )
    (net (code "98") (name "Net-(R5-A)") (class "Default")
      (node (ref "R40") (pin "1") (pinfunction "1_1") (pintype "passive"))
      (node (ref "R5") (pin "1") (pinfunction "A_1") (pintype "passive"))
    )
    (net (code "99") (name "Net-(R5-S)") (class "Default")
      (node (ref "R5") (pin "W") (pinfunction "S_W") (pintype "passive"))
      (node (ref "Y") (pin "12") (pinfunction "REF_12") (pintype "input"))
    )
    (net (code "100") (name "Net-(R7-Pad1)") (class "Default")
      (node (ref "R7") (pin "1") (pinfunction "1_1") (pintype "passive"))
      (node (ref "SD-ON") (pin "A") (pinfunction "A_A") (pintype "passive"))
    )
    (net (code "101") (name "Net-(R15-A)") (class "Default")
      (node (ref "R15") (pin "1") (pinfunction "A_1") (pintype "passive"))
      (node (ref "R39") (pin "1") (pinfunction "1_1") (pintype "passive"))
    )
    (net (code "102") (name "Net-(R15-S)") (class "Default")
      (node (ref "R15") (pin "W") (pinfunction "S_W") (pintype "passive"))
      (node (ref "X") (pin "12") (pinfunction "REF_12") (pintype "input"))
    )
    (net (code "103") (name "Net-(R23-A)") (class "Default")
      (node (ref "R23") (pin "1") (pinfunction "A_1") (pintype "passive"))
      (node (ref "R41") (pin "1") (pinfunction "1_1") (pintype "passive"))
    )
    (net (code "104") (name "Net-(R23-S)") (class "Default")
      (node (ref "R23") (pin "W") (pinfunction "S_W") (pintype "passive"))
      (node (ref "Z") (pin "12") (pinfunction "REF_12") (pintype "input"))
    )
    (net (code "105") (name "Net-(R29-A)") (class "Default")
      (node (ref "R29") (pin "1") (pinfunction "A_1") (pintype "passive"))
      (node (ref "R42") (pin "1") (pinfunction "1_1") (pintype "passive"))
    )
    (net (code "106") (name "Net-(RESET-Pad3)") (class "Default")
      (node (ref "RESET") (pin "3") (pinfunction "3_3") (pintype "passive"))
      (node (ref "RESET") (pin "4") (pinfunction "4_4") (pintype "passive"))
    )
    (net (code "107") (name "Net-(RN3A-2)") (class "Default")
      (node (ref "ON") (pin "A") (pinfunction "A_A") (pintype "passive"))
      (node (ref "RN3") (pin "8") (pinfunction "2_8") (pintype "passive"))
    )
    (net (code "108") (name "Net-(RN3B-1)") (class "Default")
      (node (ref "L") (pin "A") (pinfunction "A_A") (pintype "passive"))
      (node (ref "RN3") (pin "2") (pinfunction "1_2") (pintype "passive"))
    )
    (net (code "109") (name "Net-(RN4C-1)") (class "Default")
      (node (ref "RN4") (pin "3") (pinfunction "1_3") (pintype "passive"))
      (node (ref "TX") (pin "A") (pinfunction "A_A") (pintype "passive"))
    )
    (net (code "110") (name "Net-(RN4D-1)") (class "Default")
      (node (ref "RN4") (pin "4") (pinfunction "1_4") (pintype "passive"))
      (node (ref "RX") (pin "A") (pinfunction "A_A") (pintype "passive"))
    )
    (net (code "111") (name "Net-(U1-CB)") (class "Default")
      (node (ref "C2") (pin "2") (pinfunction "2_2") (pintype "passive"))
      (node (ref "U1") (pin "1") (pinfunction "CB_1") (pintype "passive"))
    )
    (net (code "112") (name "Net-(U1-FB)") (class "Default")
      (node (ref "R37") (pin "2") (pinfunction "2_2") (pintype "passive"))
      (node (ref "R38") (pin "1") (pinfunction "1_1") (pintype "passive"))
      (node (ref "U1") (pin "3") (pinfunction "FB_3") (pintype "passive"))
    )
    (net (code "113") (name "Net-(X-CP1)") (class "Default")
      (node (ref "C5") (pin "2") (pinfunction "2_2") (pintype "passive"))
      (node (ref "X") (pin "1") (pinfunction "CP1_1") (pintype "passive"))
    )
    (net (code "114") (name "Net-(X-CP2)") (class "Default")
      (node (ref "C5") (pin "1") (pinfunction "1_1") (pintype "passive"))
      (node (ref "X") (pin "2") (pinfunction "CP2_2") (pintype "passive"))
    )
    (net (code "115") (name "Net-(X-MS1)") (class "Default")
      (node (ref "MS-X") (pin "1") (pinfunction "1_1") (pintype "passive"))
      (node (ref "X") (pin "5") (pinfunction "MS1_5") (pintype "input"))
    )
    (net (code "116") (name "Net-(X-MS2)") (class "Default")
      (node (ref "MS-X") (pin "3") (pinfunction "3_3") (pintype "passive"))
      (node (ref "X") (pin "6") (pinfunction "MS2_6") (pintype "input"))
    )
    (net (code "117") (name "Net-(X-OUT1A)") (class "Default")
      (node (ref "X") (pin "18") (pinfunction "OUT1A_18") (pintype "output"))
      (node (ref "X-M") (pin "2") (pinfunction "2_2") (pintype "passive"))
    )
    (net (code "118") (name "Net-(X-OUT1B)") (class "Default")
      (node (ref "X") (pin "15") (pinfunction "OUT1B_15") (pintype "output"))
      (node (ref "X-M") (pin "1") (pinfunction "1_1") (pintype "passive"))
    )
    (net (code "119") (name "Net-(X-OUT2A)") (class "Default")
      (node (ref "X") (pin "19") (pinfunction "OUT2A_19") (pintype "output"))
      (node (ref "X-M") (pin "3") (pinfunction "3_3") (pintype "passive"))
    )
    (net (code "120") (name "Net-(X-OUT2B)") (class "Default")
      (node (ref "X") (pin "22") (pinfunction "OUT2B_22") (pintype "output"))
      (node (ref "X-M") (pin "4") (pinfunction "4_4") (pintype "passive"))
    )
    (net (code "121") (name "Net-(X-ROSC)") (class "Default")
      (node (ref "R2") (pin "1") (pinfunction "1_1") (pintype "passive"))
      (node (ref "X") (pin "8") (pinfunction "ROSC_8") (pintype "passive"))
    )
    (net (code "122") (name "Net-(X-SENSE1)") (class "Default")
      (node (ref "R17") (pin "1") (pinfunction "1_1") (pintype "passive"))
      (node (ref "X") (pin "17") (pinfunction "SENSE1_17") (pintype "passive"))
    )
    (net (code "123") (name "Net-(X-SENSE2)") (class "Default")
      (node (ref "R18") (pin "1") (pinfunction "1_1") (pintype "passive"))
      (node (ref "X") (pin "20") (pinfunction "SENSE2_20") (pintype "passive"))
    )
    (net (code "124") (name "Net-(X-VCP)") (class "Default")
      (node (ref "C4") (pin "2") (pinfunction "2_2") (pintype "passive"))
      (node (ref "X") (pin "3") (pinfunction "VCP_3") (pintype "passive"))
    )
    (net (code "125") (name "Net-(X-VREG)") (class "Default")
      (node (ref "C8") (pin "2") (pinfunction "2_2") (pintype "passive"))
      (node (ref "X") (pin "4") (pinfunction "VREG_4") (pintype "passive"))
    )
    (net (code "126") (name "Net-(X-~{RESET})") (class "Default")
      (node (ref "R4") (pin "2") (pinfunction "2_2") (pintype "passive"))
      (node (ref "X") (pin "7") (pinfunction "~{RESET}_7") (pintype "input"))
      (node (ref "X") (pin "9") (pinfunction "~{SLEEP}_9") (pintype "input"))
    )
    (net (code "127") (name "Net-(Y-CP1)") (class "Default")
      (node (ref "C17") (pin "2") (pinfunction "2_2") (pintype "passive"))
      (node (ref "Y") (pin "1") (pinfunction "CP1_1") (pintype "passive"))
    )
    (net (code "128") (name "Net-(Y-CP2)") (class "Default")
      (node (ref "C17") (pin "1") (pinfunction "1_1") (pintype "passive"))
      (node (ref "Y") (pin "2") (pinfunction "CP2_2") (pintype "passive"))
    )
    (net (code "129") (name "Net-(Y-MS1)") (class "Default")
      (node (ref "MS-Y") (pin "1") (pinfunction "1_1") (pintype "passive"))
      (node (ref "Y") (pin "5") (pinfunction "MS1_5") (pintype "input"))
    )
    (net (code "130") (name "Net-(Y-MS2)") (class "Default")
      (node (ref "MS-Y") (pin "3") (pinfunction "3_3") (pintype "passive"))
      (node (ref "Y") (pin "6") (pinfunction "MS2_6") (pintype "input"))
    )
    (net (code "131") (name "Net-(Y-OUT1A)") (class "Default")
      (node (ref "Y") (pin "18") (pinfunction "OUT1A_18") (pintype "output"))
      (node (ref "Y-M") (pin "2") (pinfunction "2_2") (pintype "passive"))
    )
    (net (code "132") (name "Net-(Y-OUT1B)") (class "Default")
      (node (ref "Y") (pin "15") (pinfunction "OUT1B_15") (pintype "output"))
      (node (ref "Y-M") (pin "1") (pinfunction "1_1") (pintype "passive"))
    )
    (net (code "133") (name "Net-(Y-OUT2A)") (class "Default")
      (node (ref "Y") (pin "19") (pinfunction "OUT2A_19") (pintype "output"))
      (node (ref "Y-M") (pin "3") (pinfunction "3_3") (pintype "passive"))
    )
    (net (code "134") (name "Net-(Y-OUT2B)") (class "Default")
      (node (ref "Y") (pin "22") (pinfunction "OUT2B_22") (pintype "output"))
      (node (ref "Y-M") (pin "4") (pinfunction "4_4") (pintype "passive"))
    )
    (net (code "135") (name "Net-(Y-ROSC)") (class "Default")
      (node (ref "R20") (pin "1") (pinfunction "1_1") (pintype "passive"))
      (node (ref "Y") (pin "8") (pinfunction "ROSC_8") (pintype "passive"))
    )
    (net (code "136") (name "Net-(Y-SENSE1)") (class "Default")
      (node (ref "R16") (pin "1") (pinfunction "1_1") (pintype "passive"))
      (node (ref "Y") (pin "17") (pinfunction "SENSE1_17") (pintype "passive"))
    )
    (net (code "137") (name "Net-(Y-SENSE2)") (class "Default")
      (node (ref "R19") (pin "1") (pinfunction "1_1") (pintype "passive"))
      (node (ref "Y") (pin "20") (pinfunction "SENSE2_20") (pintype "passive"))
    )
    (net (code "138") (name "Net-(Y-VCP)") (class "Default")
      (node (ref "C21") (pin "2") (pinfunction "2_2") (pintype "passive"))
      (node (ref "Y") (pin "3") (pinfunction "VCP_3") (pintype "passive"))
    )
    (net (code "139") (name "Net-(Y-VREG)") (class "Default")
      (node (ref "C19") (pin "2") (pinfunction "2_2") (pintype "passive"))
      (node (ref "Y") (pin "4") (pinfunction "VREG_4") (pintype "passive"))
    )
    (net (code "140") (name "Net-(Y-~{RESET})") (class "Default")
      (node (ref "R22") (pin "2") (pinfunction "2_2") (pintype "passive"))
      (node (ref "Y") (pin "7") (pinfunction "~{RESET}_7") (pintype "input"))
      (node (ref "Y") (pin "9") (pinfunction "~{SLEEP}_9") (pintype "input"))
    )
    (net (code "141") (name "Net-(Z-CP1)") (class "Default")
      (node (ref "C22") (pin "2") (pinfunction "2_2") (pintype "passive"))
      (node (ref "Z") (pin "1") (pinfunction "CP1_1") (pintype "passive"))
    )
    (net (code "142") (name "Net-(Z-CP2)") (class "Default")
      (node (ref "C22") (pin "1") (pinfunction "1_1") (pintype "passive"))
      (node (ref "Z") (pin "2") (pinfunction "CP2_2") (pintype "passive"))
    )
    (net (code "143") (name "Net-(Z-MS1)") (class "Default")
      (node (ref "MS-Z") (pin "1") (pinfunction "1_1") (pintype "passive"))
      (node (ref "Z") (pin "5") (pinfunction "MS1_5") (pintype "input"))
    )
    (net (code "144") (name "Net-(Z-MS2)") (class "Default")
      (node (ref "MS-Z") (pin "3") (pinfunction "3_3") (pintype "passive"))
      (node (ref "Z") (pin "6") (pinfunction "MS2_6") (pintype "input"))
    )
    (net (code "145") (name "Net-(Z-OUT1A)") (class "Default")
      (node (ref "Z") (pin "18") (pinfunction "OUT1A_18") (pintype "output"))
      (node (ref "Z-M") (pin "2") (pinfunction "2_2") (pintype "passive"))
    )
    (net (code "146") (name "Net-(Z-OUT1B)") (class "Default")
      (node (ref "Z") (pin "15") (pinfunction "OUT1B_15") (pintype "output"))
      (node (ref "Z-M") (pin "1") (pinfunction "1_1") (pintype "passive"))
    )
    (net (code "147") (name "Net-(Z-OUT2A)") (class "Default")
      (node (ref "Z") (pin "19") (pinfunction "OUT2A_19") (pintype "output"))
      (node (ref "Z-M") (pin "3") (pinfunction "3_3") (pintype "passive"))
    )
    (net (code "148") (name "Net-(Z-OUT2B)") (class "Default")
      (node (ref "Z") (pin "22") (pinfunction "OUT2B_22") (pintype "output"))
      (node (ref "Z-M") (pin "4") (pinfunction "4_4") (pintype "passive"))
    )
    (net (code "149") (name "Net-(Z-ROSC)") (class "Default")
      (node (ref "R26") (pin "1") (pinfunction "1_1") (pintype "passive"))
      (node (ref "Z") (pin "8") (pinfunction "ROSC_8") (pintype "passive"))
    )
    (net (code "150") (name "Net-(Z-SENSE1)") (class "Default")
      (node (ref "R24") (pin "1") (pinfunction "1_1") (pintype "passive"))
      (node (ref "Z") (pin "17") (pinfunction "SENSE1_17") (pintype "passive"))
    )
    (net (code "151") (name "Net-(Z-SENSE2)") (class "Default")
      (node (ref "R25") (pin "1") (pinfunction "1_1") (pintype "passive"))
      (node (ref "Z") (pin "20") (pinfunction "SENSE2_20") (pintype "passive"))
    )
    (net (code "152") (name "Net-(Z-VCP)") (class "Default")
      (node (ref "C26") (pin "2") (pinfunction "2_2") (pintype "passive"))
      (node (ref "Z") (pin "3") (pinfunction "VCP_3") (pintype "passive"))
    )
    (net (code "153") (name "Net-(Z-VREG)") (class "Default")
      (node (ref "C24") (pin "2") (pinfunction "2_2") (pintype "passive"))
      (node (ref "Z") (pin "4") (pinfunction "VREG_4") (pintype "passive"))
    )
    (net (code "154") (name "Net-(Z-~{RESET})") (class "Default")
      (node (ref "R28") (pin "2") (pinfunction "2_2") (pintype "passive"))
      (node (ref "Z") (pin "7") (pinfunction "~{RESET}_7") (pintype "input"))
      (node (ref "Z") (pin "9") (pinfunction "~{SLEEP}_9") (pintype "input"))
    )
    (net (code "155") (name "RD+") (class "Default")
      (node (ref "IC4") (pin "29") (pinfunction "D+_29") (pintype "bidirectional"))
      (node (ref "RN2") (pin "4") (pinfunction "1_4") (pintype "passive"))
    )
    (net (code "156") (name "RD-") (class "Default")
      (node (ref "IC4") (pin "30") (pinfunction "D-_30") (pintype "bidirectional"))
      (node (ref "RN2") (pin "1") (pinfunction "1_1") (pintype "passive"))
    )
    (net (code "157") (name "RESET") (class "Default")
      (node (ref "C47") (pin "2") (pinfunction "2_2") (pintype "passive"))
      (node (ref "IC3") (pin "30") (pinfunction "RESET_30") (pintype "input"))
    )
    (net (code "158") (name "RESET2") (class "Default")
      (node (ref "D4") (pin "A") (pinfunction "A_A") (pintype "passive"))
      (node (ref "IC4") (pin "24") (pinfunction "RESET(PC1/DW)_24") (pintype "input"))
      (node (ref "ICSP1") (pin "5") (pinfunction "5_5") (pintype "passive"))
      (node (ref "RN5") (pin "7") (pinfunction "2_7") (pintype "passive"))
    )
    (net (code "159") (name "RXD0") (class "Default")
      (node (ref "IC3") (pin "2") (pinfunction "(RXD0/PCIN8)PE0_2") (pintype "bidirectional"))
      (node (ref "RN4") (pin "1") (pinfunction "1_1") (pintype "passive"))
      (node (ref "RXD-TXD") (pin "2") (pinfunction "2_2") (pintype "passive"))
    )
    (net (code "160") (name "RXD1") (class "Default")
      (node (ref "IC3") (pin "45") (pinfunction "(RXD1/INT2)PD2_45") (pintype "bidirectional"))
    )
    (net (code "161") (name "RXD2") (class "Default")
      (node (ref "IC3") (pin "12") (pinfunction "PH0(RXD2)_12") (pintype "bidirectional"))
    )
    (net (code "162") (name "RXD3") (class "Default")
      (node (ref "IC3") (pin "63") (pinfunction "PJ0(RXD3/PCINT9)_63") (pintype "bidirectional"))
    )
    (net (code "163") (name "RXL") (class "Default")
      (node (ref "IC4") (pin "10") (pinfunction "(INT5/AIN3)PD4_10") (pintype "bidirectional"))
      (node (ref "RX") (pin "C") (pinfunction "C_C") (pintype "passive"))
    )
    (net (code "164") (name "SCK") (class "Default")
      (node (ref "IC3") (pin "20") (pinfunction "(SCK/PCINT1)PB1_20") (pintype "bidirectional"))
      (node (ref "ICSP") (pin "3") (pinfunction "3_3") (pintype "passive"))
      (node (ref "U8") (pin "12") (pinfunction "B2_12") (pintype "bidirectional"))
    )
    (net (code "165") (name "SCK2") (class "Default")
      (node (ref "IC4") (pin "15") (pinfunction "(SCLK/PCINT1)PB1_15") (pintype "bidirectional"))
      (node (ref "ICSP1") (pin "3") (pinfunction "3_3") (pintype "passive"))
    )
    (net (code "166") (name "SCL") (class "Default")
      (node (ref "IC3") (pin "43") (pinfunction "(SCL/INT0)PD0_43") (pintype "bidirectional"))
      (node (ref "RN1") (pin "3") (pinfunction "1_3") (pintype "passive"))
      (node (ref "SDA-SCL") (pin "2") (pinfunction "2_2") (pintype "passive"))
    )
    (net (code "167") (name "SDA") (class "Default")
      (node (ref "IC3") (pin "44") (pinfunction "(SDA/INT1)PD1_44") (pintype "bidirectional"))
      (node (ref "RN1") (pin "2") (pinfunction "1_2") (pintype "passive"))
      (node (ref "SDA-SCL") (pin "1") (pinfunction "1_1") (pintype "passive"))
    )
    (net (code "168") (name "SDCLK") (class "Default")
      (node (ref "U2") (pin "5") (pinfunction "SCK_5") (pintype "bidirectional"))
      (node (ref "U8") (pin "3") (pinfunction "A2_3") (pintype "bidirectional"))
    )
    (net (code "169") (name "SDCSH") (class "Default")
      (node (ref "U2") (pin "2") (pinfunction "CS_2") (pintype "bidirectional"))
      (node (ref "U8") (pin "5") (pinfunction "A4_5") (pintype "bidirectional"))
    )
    (net (code "170") (name "SDDI") (class "Default")
      (node (ref "U2") (pin "3") (pinfunction "DI_3") (pintype "bidirectional"))
      (node (ref "U8") (pin "4") (pinfunction "A3_4") (pintype "bidirectional"))
    )
    (net (code "171") (name "SDDO") (class "Default")
      (node (ref "U2") (pin "7") (pinfunction "DO_7") (pintype "bidirectional"))
      (node (ref "U8") (pin "2") (pinfunction "A1_2") (pintype "bidirectional"))
    )
    (net (code "172") (name "TXD0") (class "Default")
      (node (ref "IC3") (pin "3") (pinfunction "(TXD0)PE1_3") (pintype "bidirectional"))
      (node (ref "RN4") (pin "2") (pinfunction "1_2") (pintype "passive"))
      (node (ref "RXD-TXD") (pin "1") (pinfunction "1_1") (pintype "passive"))
    )
    (net (code "173") (name "TXD1") (class "Default")
      (node (ref "IC3") (pin "46") (pinfunction "(TXD1/INT3)PD3_46") (pintype "bidirectional"))
    )
    (net (code "174") (name "TXD3") (class "Default")
      (node (ref "IC3") (pin "64") (pinfunction "PJ1(TXD3/PCINT10)_64") (pintype "bidirectional"))
    )
    (net (code "175") (name "TXL") (class "Default")
      (node (ref "IC4") (pin "11") (pinfunction "(XCK/AIN4/PCINT12)PD5_11") (pintype "bidirectional"))
      (node (ref "TX") (pin "C") (pinfunction "C_C") (pintype "passive"))
    )
    (net (code "176") (name "USBVCC") (class "Default")
      (node (ref "C44") (pin "1") (pinfunction "1_1") (pintype "passive"))
      (node (ref "F1") (pin "1") (pinfunction "1_1") (pintype "passive"))
      (node (ref "IC4") (pin "31") (pinfunction "UVCC_31") (pintype "power_in"))
    )
    (net (code "177") (name "USHIELD") (class "Default")
      (node (ref "L2") (pin "2") (pinfunction "2_2") (pintype "passive"))
      (node (ref "X4") (pin "P$1") (pinfunction "P$1_P$1") (pintype "bidirectional"))
      (node (ref "X4") (pin "P$2") (pinfunction "P$2_P$2") (pintype "bidirectional"))
      (node (ref "Z1") (pin "1") (pinfunction "1_1") (pintype "passive"))
      (node (ref "Z2") (pin "1") (pinfunction "1_1") (pintype "passive"))
    )
    (net (code "178") (name "VAR") (class "Default")
      (node (ref "LCD") (pin "10") (pinfunction "10_10") (pintype "passive"))
      (node (ref "R8") (pin "W") (pinfunction "S_W") (pintype "passive"))
    )
    (net (code "179") (name "VUCAP") (class "Default")
      (node (ref "C50") (pin "1") (pinfunction "1_1") (pintype "passive"))
      (node (ref "IC4") (pin "27") (pinfunction "UCAP_27") (pintype "passive"))
    )
    (net (code "180") (name "XT1") (class "Default")
      (node (ref "C51") (pin "1") (pinfunction "1_1") (pintype "passive"))
      (node (ref "IC4") (pin "1") (pinfunction "XTAL1_1") (pintype "bidirectional"))
      (node (ref "R44") (pin "1") (pinfunction "1_1") (pintype "passive"))
      (node (ref "Y2") (pin "2") (pinfunction "2_2") (pintype "passive"))
    )
    (net (code "181") (name "XT2") (class "Default")
      (node (ref "C52") (pin "1") (pinfunction "1_1") (pintype "passive"))
      (node (ref "IC4") (pin "2") (pinfunction "XTAL2(PC0)_2") (pintype "bidirectional"))
      (node (ref "R44") (pin "2") (pinfunction "2_2") (pintype "passive"))
      (node (ref "Y2") (pin "1") (pinfunction "1_1") (pintype "passive"))
    )
    (net (code "182") (name "XTAL1") (class "Default")
      (node (ref "IC3") (pin "34") (pinfunction "XTAL1_34") (pintype "input"))
      (node (ref "R43") (pin "1") (pinfunction "1_1") (pintype "passive"))
      (node (ref "Y1") (pin "3") (pinfunction "3_3") (pintype "passive"))
    )
    (net (code "183") (name "XTAL2") (class "Default")
      (node (ref "IC3") (pin "33") (pinfunction "XTAL2_33") (pintype "output"))
      (node (ref "R43") (pin "2") (pinfunction "2_2") (pintype "passive"))
      (node (ref "Y1") (pin "1") (pinfunction "1_1") (pintype "passive"))
    )
    (net (code "184") (name "XVCC") (class "Default")
      (node (ref "F1") (pin "2") (pinfunction "2_2") (pintype "passive"))
      (node (ref "X4") (pin "1") (pinfunction "1_1") (pintype "bidirectional"))
    )
    (net (code "185") (name "unconnected-(IC3-(CLKO{slash}ICP3{slash}INT7)PE7-Pad9)") (class "Default")
      (node (ref "IC3") (pin "9") (pinfunction "(CLKO/ICP3/INT7)PE7_9") (pintype "bidirectional"))
    )
    (net (code "186") (name "unconnected-(IC3-(ICP1)PD4-Pad47)") (class "Default")
      (node (ref "IC3") (pin "47") (pinfunction "(ICP1)PD4_47") (pintype "bidirectional"))
    )
    (net (code "187") (name "unconnected-(IC3-(T1)PD6-Pad49)") (class "Default")
      (node (ref "IC3") (pin "49") (pinfunction "(T1)PD6_49") (pintype "bidirectional"))
    )
    (net (code "188") (name "unconnected-(IC3-(T3{slash}INT6)PE6-Pad8)") (class "Default")
      (node (ref "IC3") (pin "8") (pinfunction "(T3/INT6)PE6_8") (pintype "bidirectional"))
    )
    (net (code "189") (name "unconnected-(IC3-(TOSC1)PG4-Pad29)") (class "Default")
      (node (ref "IC3") (pin "29") (pinfunction "(TOSC1)PG4_29") (pintype "bidirectional"))
    )
    (net (code "190") (name "unconnected-(IC3-(TOSC2)PG3-Pad28)") (class "Default")
      (node (ref "IC3") (pin "28") (pinfunction "(TOSC2)PG3_28") (pintype "bidirectional"))
    )
    (net (code "191") (name "unconnected-(IC3-(XCK0{slash}AIN0)PE2-Pad4)") (class "Default")
      (node (ref "IC3") (pin "4") (pinfunction "(XCK0/AIN0)PE2_4") (pintype "bidirectional"))
    )
    (net (code "192") (name "unconnected-(IC3-(XCK1)PD5-Pad48)") (class "Default")
      (node (ref "IC3") (pin "48") (pinfunction "(XCK1)PD5_48") (pintype "bidirectional"))
    )
    (net (code "193") (name "unconnected-(IC3-PH2(XCK2)-Pad14)") (class "Default")
      (node (ref "IC3") (pin "14") (pinfunction "PH2(XCK2)_14") (pintype "bidirectional"))
    )
    (net (code "194") (name "unconnected-(IC3-PH7(T4)-Pad27)") (class "Default")
      (node (ref "IC3") (pin "27") (pinfunction "PH7(T4)_27") (pintype "bidirectional"))
    )
    (net (code "195") (name "unconnected-(IC3-PJ2(XCK3{slash}PCINT11)-Pad65)") (class "Default")
      (node (ref "IC3") (pin "65") (pinfunction "PJ2(XCK3/PCINT11)_65") (pintype "bidirectional"))
    )
    (net (code "196") (name "unconnected-(IC3-PJ3(PCINT12)-Pad66)") (class "Default")
      (node (ref "IC3") (pin "66") (pinfunction "PJ3(PCINT12)_66") (pintype "bidirectional"))
    )
    (net (code "197") (name "unconnected-(IC3-PJ4(PCINT13)-Pad67)") (class "Default")
      (node (ref "IC3") (pin "67") (pinfunction "PJ4(PCINT13)_67") (pintype "bidirectional"))
    )
    (net (code "198") (name "unconnected-(IC3-PJ5(PCINT14)-Pad68)") (class "Default")
      (node (ref "IC3") (pin "68") (pinfunction "PJ5(PCINT14)_68") (pintype "bidirectional"))
    )
    (net (code "199") (name "unconnected-(IC3-PJ6(PCINT15)-Pad69)") (class "Default")
      (node (ref "IC3") (pin "69") (pinfunction "PJ6(PCINT15)_69") (pintype "bidirectional"))
    )
    (net (code "200") (name "unconnected-(IC3-PJ7-Pad79)") (class "Default")
      (node (ref "IC3") (pin "79") (pinfunction "PJ7_79") (pintype "bidirectional"))
    )
    (net (code "201") (name "unconnected-(IC4-(AIN0{slash}INT1)PD1-Pad7)") (class "Default")
      (node (ref "IC4") (pin "7") (pinfunction "(AIN0/INT1)PD1_7") (pintype "bidirectional"))
    )
    (net (code "202") (name "unconnected-(IC4-(AIN2{slash}PCINT11)PC2-Pad5)") (class "Default")
      (node (ref "IC4") (pin "5") (pinfunction "(AIN2/PCINT11)PC2_5") (pintype "bidirectional"))
    )
    (net (code "203") (name "unconnected-(IC4-(INT4{slash}ICP1{slash}CLK0)PC7-Pad22)") (class "Default")
      (node (ref "IC4") (pin "22") (pinfunction "(INT4/ICP1/CLK0)PC7_22") (pintype "bidirectional"))
    )
    (net (code "204") (name "unconnected-(IC4-(OC0B{slash}INT0)PD0-Pad6)") (class "Default")
      (node (ref "IC4") (pin "6") (pinfunction "(OC0B/INT0)PD0_6") (pintype "bidirectional"))
    )
    (net (code "205") (name "unconnected-(IC4-(OC1A{slash}PCINT8)PC6-Pad23)") (class "Default")
      (node (ref "IC4") (pin "23") (pinfunction "(OC1A/PCINT8)PC6_23") (pintype "bidirectional"))
    )
    (net (code "206") (name "unconnected-(IC4-(PCINT5)PB5-Pad19)") (class "Default")
      (node (ref "IC4") (pin "19") (pinfunction "(PCINT5)PB5_19") (pintype "bidirectional"))
    )
    (net (code "207") (name "unconnected-(IC4-(PCINT6)PB6-Pad20)") (class "Default")
      (node (ref "IC4") (pin "20") (pinfunction "(PCINT6)PB6_20") (pintype "bidirectional"))
    )
    (net (code "208") (name "unconnected-(IC4-(PCINT7{slash}OC0A{slash}OC1C)PB7-Pad21)") (class "Default")
      (node (ref "IC4") (pin "21") (pinfunction "(PCINT7/OC0A/OC1C)PB7_21") (pintype "bidirectional"))
    )
    (net (code "209") (name "unconnected-(IC4-(PCINT9{slash}OC1B)PC5-Pad25)") (class "Default")
      (node (ref "IC4") (pin "25") (pinfunction "(PCINT9/OC1B)PC5_25") (pintype "bidirectional"))
    )
    (net (code "210") (name "unconnected-(IC4-(PCINT10)PC4-Pad26)") (class "Default")
      (node (ref "IC4") (pin "26") (pinfunction "(PCINT10)PC4_26") (pintype "bidirectional"))
    )
    (net (code "211") (name "unconnected-(IC4-(RTS{slash}AIN5{slash}INT6)PD6-Pad12)") (class "Default")
      (node (ref "IC4") (pin "12") (pinfunction "(RTS/AIN5/INT6)PD6_12") (pintype "bidirectional"))
    )
    (net (code "212") (name "unconnected-(IC4-(SS{slash}PCINT0)PB0-Pad14)") (class "Default")
      (node (ref "IC4") (pin "14") (pinfunction "(SS/PCINT0)PB0_14") (pintype "bidirectional"))
    )
    (net (code "213") (name "unconnected-(IC4-(T1{slash}PCINT4)PB4-Pad18)") (class "Default")
      (node (ref "IC4") (pin "18") (pinfunction "(T1/PCINT4)PB4_18") (pintype "bidirectional"))
    )
    (net (code "214") (name "unconnected-(ICSP-Pad5)") (class "Default")
      (node (ref "ICSP") (pin "5") (pinfunction "5_5") (pintype "passive"))
    )
    (net (code "215") (name "unconnected-(RESET-EX-Pad2)") (class "Default")
      (node (ref "RESET-EX") (pin "2") (pinfunction "2_2") (pintype "passive"))
    )
    (net (code "216") (name "unconnected-(RN1-Pad1)") (class "Default")
      (node (ref "RN1") (pin "1") (pinfunction "1_1") (pintype "passive"))
    )
    (net (code "217") (name "unconnected-(RN1A-2-Pad8)") (class "Default")
      (node (ref "RN1") (pin "8") (pinfunction "2_8") (pintype "passive"))
    )
    (net (code "218") (name "unconnected-(RN1D-1-Pad4)") (class "Default")
      (node (ref "RN1") (pin "4") (pinfunction "1_4") (pintype "passive"))
    )
    (net (code "219") (name "unconnected-(RN1D-2-Pad5)") (class "Default")
      (node (ref "RN1") (pin "5") (pinfunction "2_5") (pintype "passive"))
    )
    (net (code "220") (name "unconnected-(RN2B-1-Pad2)") (class "Default")
      (node (ref "RN2") (pin "2") (pinfunction "1_2") (pintype "passive"))
    )
    (net (code "221") (name "unconnected-(RN2B-2-Pad7)") (class "Default")
      (node (ref "RN2") (pin "7") (pinfunction "2_7") (pintype "passive"))
    )
    (net (code "222") (name "unconnected-(RN2C-1-Pad3)") (class "Default")
      (node (ref "RN2") (pin "3") (pinfunction "1_3") (pintype "passive"))
    )
    (net (code "223") (name "unconnected-(RN2C-2-Pad6)") (class "Default")
      (node (ref "RN2") (pin "6") (pinfunction "2_6") (pintype "passive"))
    )
    (net (code "224") (name "unconnected-(RN3C-1-Pad3)") (class "Default")
      (node (ref "RN3") (pin "3") (pinfunction "1_3") (pintype "passive"))
    )
    (net (code "225") (name "unconnected-(RN3C-2-Pad6)") (class "Default")
      (node (ref "RN3") (pin "6") (pinfunction "2_6") (pintype "passive"))
    )
    (net (code "226") (name "unconnected-(U2-NC-Pad1)") (class "Default")
      (node (ref "U2") (pin "1") (pinfunction "NC_1") (pintype "bidirectional"))
    )
    (net (code "227") (name "unconnected-(U2-RSV-Pad8)") (class "Default")
      (node (ref "U2") (pin "8") (pinfunction "RSV_8") (pintype "bidirectional"))
    )
    (net (code "228") (name "unconnected-(X-STOP-Pad2)") (class "Default")
      (node (ref "X-STOP") (pin "2") (pinfunction "2_2") (pintype "passive"))
    )
    (net (code "229") (name "unconnected-(Y-STOP-Pad2)") (class "Default")
      (node (ref "Y-STOP") (pin "2") (pinfunction "2_2") (pintype "passive"))
    )
    (net (code "230") (name "unconnected-(Z-STOP_MIN-Pad2)") (class "Default")
      (node (ref "Z-STOP_MIN") (pin "2") (pinfunction "2_2") (pintype "passive"))
    )
  )
)
